# RF_in_v2.net
KiCad netlist of a schematic drawn in Altium Designer
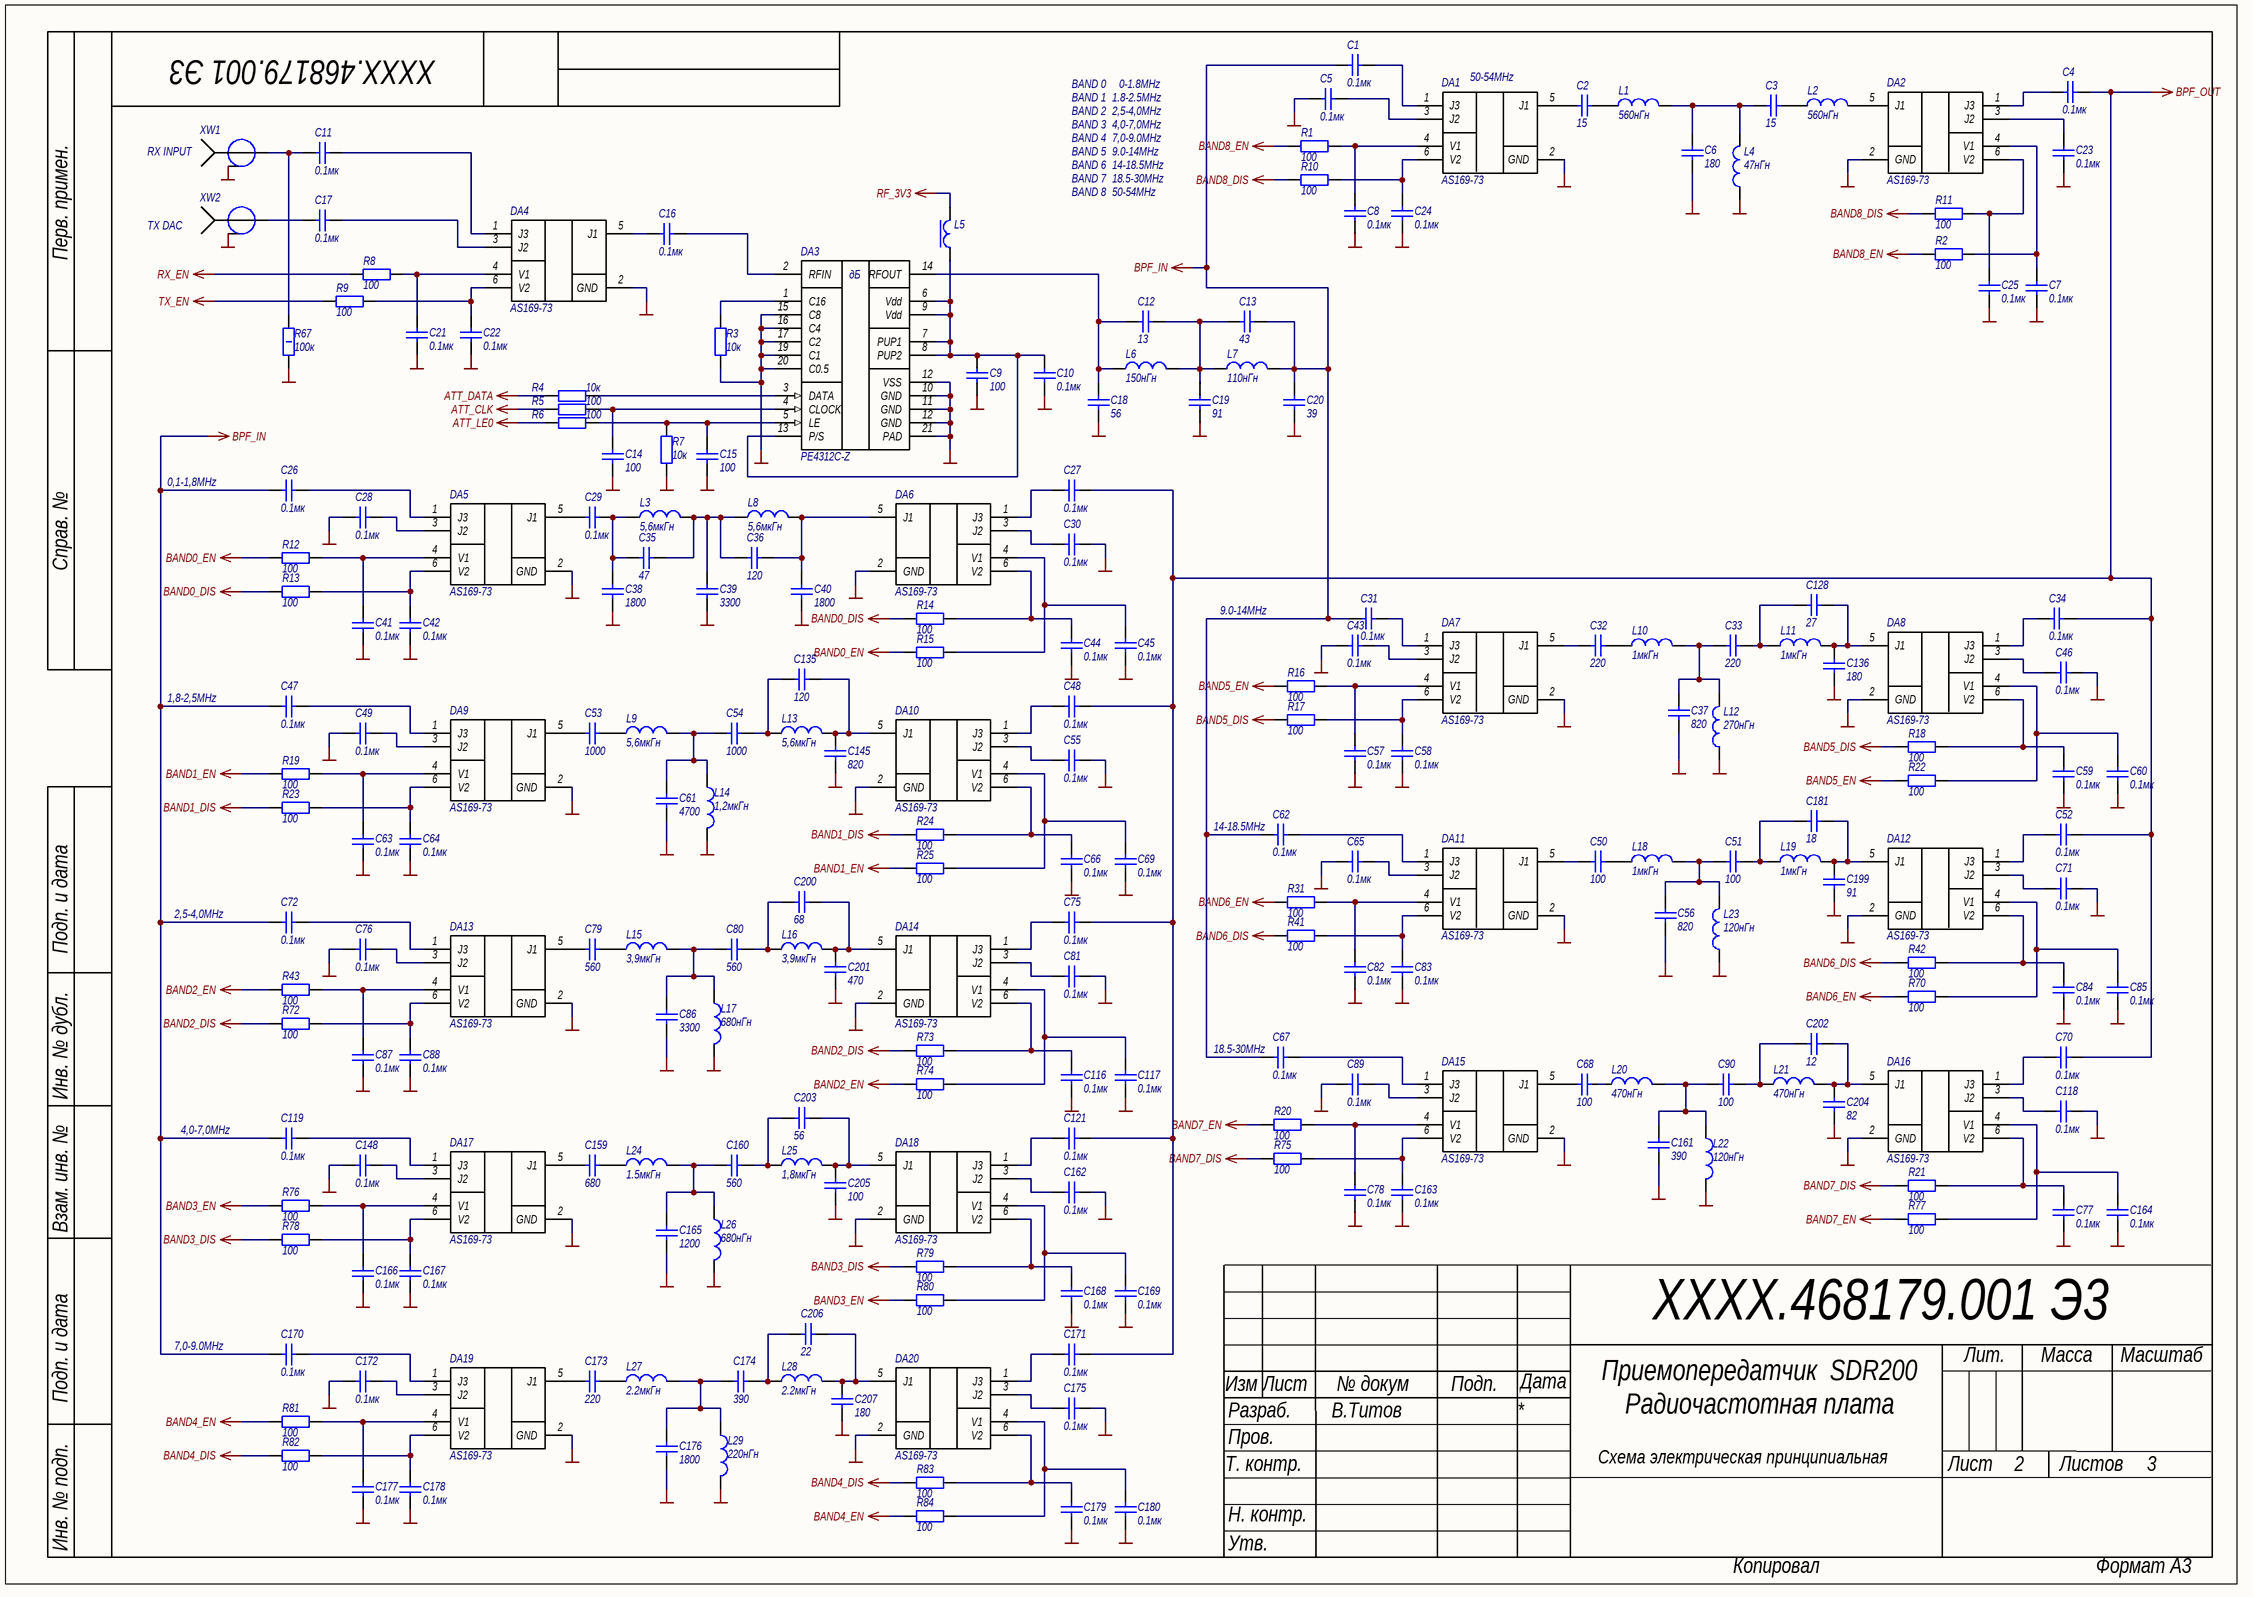
[diagram p0: RF_in_v2.SchDoc]

(export (version "E")
  (design (tool "Eeschema 10.0.6"))
  (components
    (comp (ref "C1")
      (value "0.1мк")
      (footprint "CAPC1005X06N")
      (description "Кер. ЧИП-конденсатор")
      (fields (field (name "TOLERANCE") "±10%"))
      (libsource (lib "nels") (part "Кер.ЧИП конд. 0402 0.1мкФ X7R 10%, 16В"))
    )
    (comp (ref "C2")
      (value "15")
      (footprint "CAPC1005X06N")
      (description "Кер. ЧИП-конденсатор")
      (fields (field (name "TOLERANCE") "±5%"))
      (libsource (lib "nels_caps") (part "Кер.ЧИП конд. 0402 15пФ NPO 5%, 50В"))
    )
    (comp (ref "C3")
      (value "15")
      (footprint "CAPC1005X06N")
      (description "Кер. ЧИП-конденсатор")
      (fields (field (name "TOLERANCE") "±5%"))
      (libsource (lib "nels_caps") (part "Кер.ЧИП конд. 0402 15пФ NPO 5%, 50В"))
    )
    (comp (ref "C4")
      (value "0.1мк")
      (footprint "CAPC1005X06N")
      (description "Кер. ЧИП-конденсатор")
      (fields (field (name "TOLERANCE") "±10%"))
      (libsource (lib "nels") (part "Кер.ЧИП конд. 0402 0.1мкФ X7R 10%, 16В"))
    )
    (comp (ref "C5")
      (value "0.1мк")
      (footprint "CAPC1005X06N")
      (description "Кер. ЧИП-конденсатор")
      (fields (field (name "TOLERANCE") "±10%"))
      (libsource (lib "nels") (part "Кер.ЧИП конд. 0402 0.1мкФ X7R 10%, 16В"))
    )
    (comp (ref "C6")
      (value "180")
      (footprint "CAPC1005X06N")
      (description "Кер. ЧИП-конденсатор")
      (fields (field (name "TOLERANCE") "±5%"))
      (libsource (lib "nels_caps") (part "Кер.ЧИП конд. 0402 180пФ NPO 5%, 50В"))
    )
    (comp (ref "C7")
      (value "0.1мк")
      (footprint "CAPC1005X06N")
      (description "Кер. ЧИП-конденсатор")
      (fields (field (name "TOLERANCE") "±10%"))
      (libsource (lib "nels") (part "Кер.ЧИП конд. 0402 0.1мкФ X7R 10%, 16В"))
    )
    (comp (ref "C8")
      (value "0.1мк")
      (footprint "CAPC1005X06N")
      (description "Кер. ЧИП-конденсатор")
      (fields (field (name "TOLERANCE") "±10%"))
      (libsource (lib "nels") (part "Кер.ЧИП конд. 0402 0.1мкФ X7R 10%, 16В"))
    )
    (comp (ref "C9")
      (value "100")
      (footprint "CAPC1005X06N")
      (description "Кер. ЧИП-конденсатор")
      (fields (field (name "TOLERANCE") "±5%"))
      (libsource (lib "nels_caps") (part "Кер.ЧИП конд. 0402 100пФ NPO 5%, 50В"))
    )
    (comp (ref "C10")
      (value "0.1мк")
      (footprint "CAPC1005X06N")
      (description "Кер. ЧИП-конденсатор")
      (fields (field (name "TOLERANCE") "±10%"))
      (libsource (lib "nels") (part "Кер.ЧИП конд. 0402 0.1мкФ X7R 10%, 16В"))
    )
    (comp (ref "C11")
      (value "0.1мк")
      (footprint "CAPC1005X06N")
      (description "Кер. ЧИП-конденсатор")
      (fields (field (name "TOLERANCE") "±10%"))
      (libsource (lib "nels") (part "Кер.ЧИП конд. 0402 0.1мкФ X7R 10%, 16В"))
    )
    (comp (ref "C12")
      (value "13")
      (footprint "CAPC1005X06N")
      (description "Кер. ЧИП-конденсатор")
      (fields (field (name "TOLERANCE") "±5%"))
      (libsource (lib "nels_caps") (part "Кер.ЧИП конд. 0402 13пФ NPO 5%, 50В"))
    )
    (comp (ref "C13")
      (value "43")
      (footprint "CAPC1005X06N")
      (description "Кер. ЧИП-конденсатор")
      (fields (field (name "TOLERANCE") "±5%"))
      (libsource (lib "nels_caps") (part "Кер.ЧИП конд. 0402 43пФ NPO 5%, 50В"))
    )
    (comp (ref "C14")
      (value "100")
      (footprint "CAPC1005X06N")
      (description "Кер. ЧИП-конденсатор")
      (fields (field (name "TOLERANCE") "±5%"))
      (libsource (lib "nels_caps") (part "Кер.ЧИП конд. 0402 100пФ NPO 5%, 50В"))
    )
    (comp (ref "C15")
      (value "100")
      (footprint "CAPC1005X06N")
      (description "Кер. ЧИП-конденсатор")
      (fields (field (name "TOLERANCE") "±5%"))
      (libsource (lib "nels_caps") (part "Кер.ЧИП конд. 0402 100пФ NPO 5%, 50В"))
    )
    (comp (ref "C16")
      (value "0.1мк")
      (footprint "CAPC1005X06N")
      (description "Кер. ЧИП-конденсатор")
      (fields (field (name "TOLERANCE") "±10%"))
      (libsource (lib "nels") (part "Кер.ЧИП конд. 0402 0.1мкФ X7R 10%, 16В"))
    )
    (comp (ref "C17")
      (value "0.1мк")
      (footprint "CAPC1005X06N")
      (description "Кер. ЧИП-конденсатор")
      (fields (field (name "TOLERANCE") "±10%"))
      (libsource (lib "nels") (part "Кер.ЧИП конд. 0402 0.1мкФ X7R 10%, 16В"))
    )
    (comp (ref "C18")
      (value "56")
      (footprint "CAPC1005X06N")
      (description "Кер. ЧИП-конденсатор")
      (fields (field (name "TOLERANCE") "±5%"))
      (libsource (lib "nels_caps") (part "Кер.ЧИП конд. 0402 56пФ NPO 5%, 50В"))
    )
    (comp (ref "C19")
      (value "91")
      (footprint "CAPC1005X06N")
      (description "Кер. ЧИП-конденсатор")
      (fields (field (name "TOLERANCE") "±5%"))
      (libsource (lib "nels_caps") (part "Кер.ЧИП конд. 0402 91пФ NPO 5%, 50В"))
    )
    (comp (ref "C20")
      (value "39")
      (footprint "CAPC1005X06N")
      (description "Кер. ЧИП-конденсатор")
      (fields (field (name "TOLERANCE") "±5%"))
      (libsource (lib "nels_caps") (part "Кер.ЧИП конд. 0402 39пФ NPO 5%, 50В"))
    )
    (comp (ref "C21")
      (value "0.1мк")
      (footprint "CAPC1005X06N")
      (description "Кер. ЧИП-конденсатор")
      (fields (field (name "TOLERANCE") "±10%"))
      (libsource (lib "nels") (part "Кер.ЧИП конд. 0402 0.1мкФ X7R 10%, 16В"))
    )
    (comp (ref "C22")
      (value "0.1мк")
      (footprint "CAPC1005X06N")
      (description "Кер. ЧИП-конденсатор")
      (fields (field (name "TOLERANCE") "±10%"))
      (libsource (lib "nels") (part "Кер.ЧИП конд. 0402 0.1мкФ X7R 10%, 16В"))
    )
    (comp (ref "C23")
      (value "0.1мк")
      (footprint "CAPC1005X06N")
      (description "Кер. ЧИП-конденсатор")
      (fields (field (name "TOLERANCE") "±10%"))
      (libsource (lib "nels") (part "Кер.ЧИП конд. 0402 0.1мкФ X7R 10%, 16В"))
    )
    (comp (ref "C24")
      (value "0.1мк")
      (footprint "CAPC1005X06N")
      (description "Кер. ЧИП-конденсатор")
      (fields (field (name "TOLERANCE") "±10%"))
      (libsource (lib "nels") (part "Кер.ЧИП конд. 0402 0.1мкФ X7R 10%, 16В"))
    )
    (comp (ref "C25")
      (value "0.1мк")
      (footprint "CAPC1005X06N")
      (description "Кер. ЧИП-конденсатор")
      (fields (field (name "TOLERANCE") "±10%"))
      (libsource (lib "nels") (part "Кер.ЧИП конд. 0402 0.1мкФ X7R 10%, 16В"))
    )
    (comp (ref "C26")
      (value "0.1мк")
      (footprint "CAPC1005X06N")
      (description "Кер. ЧИП-конденсатор")
      (fields (field (name "TOLERANCE") "±10%"))
      (libsource (lib "nels") (part "Кер.ЧИП конд. 0402 0.1мкФ X7R 10%, 16В"))
    )
    (comp (ref "C27")
      (value "0.1мк")
      (footprint "CAPC1005X06N")
      (description "Кер. ЧИП-конденсатор")
      (fields (field (name "TOLERANCE") "±10%"))
      (libsource (lib "nels") (part "Кер.ЧИП конд. 0402 0.1мкФ X7R 10%, 16В"))
    )
    (comp (ref "C28")
      (value "0.1мк")
      (footprint "CAPC1005X06N")
      (description "Кер. ЧИП-конденсатор")
      (fields (field (name "TOLERANCE") "±10%"))
      (libsource (lib "nels") (part "Кер.ЧИП конд. 0402 0.1мкФ X7R 10%, 16В"))
    )
    (comp (ref "C29")
      (value "0.1мк")
      (footprint "CAPC1005X06N")
      (description "Кер. ЧИП-конденсатор")
      (fields (field (name "TOLERANCE") "±10%"))
      (libsource (lib "nels") (part "Кер.ЧИП конд. 0402 0.1мкФ X7R 10%, 16В"))
    )
    (comp (ref "C30")
      (value "0.1мк")
      (footprint "CAPC1005X06N")
      (description "Кер. ЧИП-конденсатор")
      (fields (field (name "TOLERANCE") "±10%"))
      (libsource (lib "nels") (part "Кер.ЧИП конд. 0402 0.1мкФ X7R 10%, 16В"))
    )
    (comp (ref "C31")
      (value "0.1мк")
      (footprint "CAPC1005X06N")
      (description "Кер. ЧИП-конденсатор")
      (fields (field (name "TOLERANCE") "±10%"))
      (libsource (lib "nels") (part "Кер.ЧИП конд. 0402 0.1мкФ X7R 10%, 16В"))
    )
    (comp (ref "C32")
      (value "220")
      (footprint "CAPC1005X06N")
      (description "Кер. ЧИП-конденсатор")
      (fields (field (name "TOLERANCE") "±5%"))
      (libsource (lib "nels_caps") (part "Кер.ЧИП конд. 0402 220пФ NPO 5%, 50В"))
    )
    (comp (ref "C33")
      (value "220")
      (footprint "CAPC1005X06N")
      (description "Кер. ЧИП-конденсатор")
      (fields (field (name "TOLERANCE") "±5%"))
      (libsource (lib "nels_caps") (part "Кер.ЧИП конд. 0402 220пФ NPO 5%, 50В"))
    )
    (comp (ref "C34")
      (value "0.1мк")
      (footprint "CAPC1005X06N")
      (description "Кер. ЧИП-конденсатор")
      (fields (field (name "TOLERANCE") "±10%"))
      (libsource (lib "nels") (part "Кер.ЧИП конд. 0402 0.1мкФ X7R 10%, 16В"))
    )
    (comp (ref "C35")
      (value "47")
      (footprint "CAPC1005X06N")
      (description "Кер. ЧИП-конденсатор")
      (fields (field (name "TOLERANCE") "±5%"))
      (libsource (lib "nels_caps") (part "Кер.ЧИП конд. 0402 47пФ NPO 5%, 50В"))
    )
    (comp (ref "C36")
      (value "120")
      (footprint "CAPC1005X06N")
      (description "Кер. ЧИП-конденсатор")
      (fields (field (name "TOLERANCE") "±5%"))
      (libsource (lib "nels_caps") (part "Кер.ЧИП конд. 0402 120пФ NPO 5%, 50В"))
    )
    (comp (ref "C37")
      (value "820")
      (footprint "CAPC1005X06N")
      (description "Кер. ЧИП-конденсатор")
      (fields (field (name "TOLERANCE") "±5%"))
      (libsource (lib "nels_caps") (part "Кер.ЧИП конд. 0402 820пФ NP0 5%, 50В"))
    )
    (comp (ref "C38")
      (value "1800")
      (footprint "CAPC1005X06N")
      (description "Кер. ЧИП-конденсатор")
      (fields (field (name "TOLERANCE") "±20%"))
      (libsource (lib "nels_caps") (part "Кер.ЧИП конд. 0402 1800пФ X7R 10%, 50В"))
    )
    (comp (ref "C39")
      (value "3300")
      (footprint "CAPC1005X06N")
      (description "Кер. ЧИП-конденсатор")
      (fields (field (name "TOLERANCE") "±20%"))
      (libsource (lib "nels_caps") (part "Кер.ЧИП конд. 0402 3300пФ X7R 10%, 50В"))
    )
    (comp (ref "C40")
      (value "1800")
      (footprint "CAPC1005X06N")
      (description "Кер. ЧИП-конденсатор")
      (fields (field (name "TOLERANCE") "±20%"))
      (libsource (lib "nels_caps") (part "Кер.ЧИП конд. 0402 1800пФ X7R 10%, 50В"))
    )
    (comp (ref "C41")
      (value "0.1мк")
      (footprint "CAPC1005X06N")
      (description "Кер. ЧИП-конденсатор")
      (fields (field (name "TOLERANCE") "±10%"))
      (libsource (lib "nels") (part "Кер.ЧИП конд. 0402 0.1мкФ X7R 10%, 16В"))
    )
    (comp (ref "C42")
      (value "0.1мк")
      (footprint "CAPC1005X06N")
      (description "Кер. ЧИП-конденсатор")
      (fields (field (name "TOLERANCE") "±10%"))
      (libsource (lib "nels") (part "Кер.ЧИП конд. 0402 0.1мкФ X7R 10%, 16В"))
    )
    (comp (ref "C43")
      (value "0.1мк")
      (footprint "CAPC1005X06N")
      (description "Кер. ЧИП-конденсатор")
      (fields (field (name "TOLERANCE") "±10%"))
      (libsource (lib "nels") (part "Кер.ЧИП конд. 0402 0.1мкФ X7R 10%, 16В"))
    )
    (comp (ref "C44")
      (value "0.1мк")
      (footprint "CAPC1005X06N")
      (description "Кер. ЧИП-конденсатор")
      (fields (field (name "TOLERANCE") "±10%"))
      (libsource (lib "nels") (part "Кер.ЧИП конд. 0402 0.1мкФ X7R 10%, 16В"))
    )
    (comp (ref "C45")
      (value "0.1мк")
      (footprint "CAPC1005X06N")
      (description "Кер. ЧИП-конденсатор")
      (fields (field (name "TOLERANCE") "±10%"))
      (libsource (lib "nels") (part "Кер.ЧИП конд. 0402 0.1мкФ X7R 10%, 16В"))
    )
    (comp (ref "C46")
      (value "0.1мк")
      (footprint "CAPC1005X06N")
      (description "Кер. ЧИП-конденсатор")
      (fields (field (name "TOLERANCE") "±10%"))
      (libsource (lib "nels") (part "Кер.ЧИП конд. 0402 0.1мкФ X7R 10%, 16В"))
    )
    (comp (ref "C47")
      (value "0.1мк")
      (footprint "CAPC1005X06N")
      (description "Кер. ЧИП-конденсатор")
      (fields (field (name "TOLERANCE") "±10%"))
      (libsource (lib "nels") (part "Кер.ЧИП конд. 0402 0.1мкФ X7R 10%, 16В"))
    )
    (comp (ref "C48")
      (value "0.1мк")
      (footprint "CAPC1005X06N")
      (description "Кер. ЧИП-конденсатор")
      (fields (field (name "TOLERANCE") "±10%"))
      (libsource (lib "nels") (part "Кер.ЧИП конд. 0402 0.1мкФ X7R 10%, 16В"))
    )
    (comp (ref "C49")
      (value "0.1мк")
      (footprint "CAPC1005X06N")
      (description "Кер. ЧИП-конденсатор")
      (fields (field (name "TOLERANCE") "±10%"))
      (libsource (lib "nels") (part "Кер.ЧИП конд. 0402 0.1мкФ X7R 10%, 16В"))
    )
    (comp (ref "C50")
      (value "100")
      (footprint "CAPC1005X06N")
      (description "Кер. ЧИП-конденсатор")
      (fields (field (name "TOLERANCE") "±5%"))
      (libsource (lib "nels_caps") (part "Кер.ЧИП конд. 0402 100пФ NPO 5%, 50В"))
    )
    (comp (ref "C51")
      (value "100")
      (footprint "CAPC1005X06N")
      (description "Кер. ЧИП-конденсатор")
      (fields (field (name "TOLERANCE") "±5%"))
      (libsource (lib "nels_caps") (part "Кер.ЧИП конд. 0402 100пФ NPO 5%, 50В"))
    )
    (comp (ref "C52")
      (value "0.1мк")
      (footprint "CAPC1005X06N")
      (description "Кер. ЧИП-конденсатор")
      (fields (field (name "TOLERANCE") "±10%"))
      (libsource (lib "nels") (part "Кер.ЧИП конд. 0402 0.1мкФ X7R 10%, 16В"))
    )
    (comp (ref "C53")
      (value "1000")
      (footprint "CAPC1005X06N")
      (description "Кер. ЧИП-конденсатор")
      (fields (field (name "TOLERANCE") "±5%"))
      (libsource (lib "nels_caps") (part "Кер.ЧИП конд. 0402 1000пФ NP0 5%, 50В"))
    )
    (comp (ref "C54")
      (value "1000")
      (footprint "CAPC1005X06N")
      (description "Кер. ЧИП-конденсатор")
      (fields (field (name "TOLERANCE") "±5%"))
      (libsource (lib "nels_caps") (part "Кер.ЧИП конд. 0402 1000пФ NP0 5%, 50В"))
    )
    (comp (ref "C55")
      (value "0.1мк")
      (footprint "CAPC1005X06N")
      (description "Кер. ЧИП-конденсатор")
      (fields (field (name "TOLERANCE") "±10%"))
      (libsource (lib "nels") (part "Кер.ЧИП конд. 0402 0.1мкФ X7R 10%, 16В"))
    )
    (comp (ref "C56")
      (value "820")
      (footprint "CAPC1005X06N")
      (description "Кер. ЧИП-конденсатор")
      (fields (field (name "TOLERANCE") "±5%"))
      (libsource (lib "nels_caps") (part "Кер.ЧИП конд. 0402 820пФ NP0 5%, 50В"))
    )
    (comp (ref "C57")
      (value "0.1мк")
      (footprint "CAPC1005X06N")
      (description "Кер. ЧИП-конденсатор")
      (fields (field (name "TOLERANCE") "±10%"))
      (libsource (lib "nels") (part "Кер.ЧИП конд. 0402 0.1мкФ X7R 10%, 16В"))
    )
    (comp (ref "C58")
      (value "0.1мк")
      (footprint "CAPC1005X06N")
      (description "Кер. ЧИП-конденсатор")
      (fields (field (name "TOLERANCE") "±10%"))
      (libsource (lib "nels") (part "Кер.ЧИП конд. 0402 0.1мкФ X7R 10%, 16В"))
    )
    (comp (ref "C59")
      (value "0.1мк")
      (footprint "CAPC1005X06N")
      (description "Кер. ЧИП-конденсатор")
      (fields (field (name "TOLERANCE") "±10%"))
      (libsource (lib "nels") (part "Кер.ЧИП конд. 0402 0.1мкФ X7R 10%, 16В"))
    )
    (comp (ref "C60")
      (value "0.1мк")
      (footprint "CAPC1005X06N")
      (description "Кер. ЧИП-конденсатор")
      (fields (field (name "TOLERANCE") "±10%"))
      (libsource (lib "nels") (part "Кер.ЧИП конд. 0402 0.1мкФ X7R 10%, 16В"))
    )
    (comp (ref "C61")
      (value "4700")
      (footprint "CAPC1005X06N")
      (description "Кер. ЧИП-конденсатор")
      (fields (field (name "TOLERANCE") "±20%"))
      (libsource (lib "nels_caps") (part "Кер.ЧИП конд. 0402 4700пФ X7R 10%, 50В"))
    )
    (comp (ref "C62")
      (value "0.1мк")
      (footprint "CAPC1005X06N")
      (description "Кер. ЧИП-конденсатор")
      (fields (field (name "TOLERANCE") "±10%"))
      (libsource (lib "nels") (part "Кер.ЧИП конд. 0402 0.1мкФ X7R 10%, 16В"))
    )
    (comp (ref "C63")
      (value "0.1мк")
      (footprint "CAPC1005X06N")
      (description "Кер. ЧИП-конденсатор")
      (fields (field (name "TOLERANCE") "±10%"))
      (libsource (lib "nels") (part "Кер.ЧИП конд. 0402 0.1мкФ X7R 10%, 16В"))
    )
    (comp (ref "C64")
      (value "0.1мк")
      (footprint "CAPC1005X06N")
      (description "Кер. ЧИП-конденсатор")
      (fields (field (name "TOLERANCE") "±10%"))
      (libsource (lib "nels") (part "Кер.ЧИП конд. 0402 0.1мкФ X7R 10%, 16В"))
    )
    (comp (ref "C65")
      (value "0.1мк")
      (footprint "CAPC1005X06N")
      (description "Кер. ЧИП-конденсатор")
      (fields (field (name "TOLERANCE") "±10%"))
      (libsource (lib "nels") (part "Кер.ЧИП конд. 0402 0.1мкФ X7R 10%, 16В"))
    )
    (comp (ref "C66")
      (value "0.1мк")
      (footprint "CAPC1005X06N")
      (description "Кер. ЧИП-конденсатор")
      (fields (field (name "TOLERANCE") "±10%"))
      (libsource (lib "nels") (part "Кер.ЧИП конд. 0402 0.1мкФ X7R 10%, 16В"))
    )
    (comp (ref "C67")
      (value "0.1мк")
      (footprint "CAPC1005X06N")
      (description "Кер. ЧИП-конденсатор")
      (fields (field (name "TOLERANCE") "±10%"))
      (libsource (lib "nels") (part "Кер.ЧИП конд. 0402 0.1мкФ X7R 10%, 16В"))
    )
    (comp (ref "C68")
      (value "100")
      (footprint "CAPC1005X06N")
      (description "Кер. ЧИП-конденсатор")
      (fields (field (name "TOLERANCE") "±5%"))
      (libsource (lib "nels_caps") (part "Кер.ЧИП конд. 0402 100пФ NPO 5%, 50В"))
    )
    (comp (ref "C69")
      (value "0.1мк")
      (footprint "CAPC1005X06N")
      (description "Кер. ЧИП-конденсатор")
      (fields (field (name "TOLERANCE") "±10%"))
      (libsource (lib "nels") (part "Кер.ЧИП конд. 0402 0.1мкФ X7R 10%, 16В"))
    )
    (comp (ref "C70")
      (value "0.1мк")
      (footprint "CAPC1005X06N")
      (description "Кер. ЧИП-конденсатор")
      (fields (field (name "TOLERANCE") "±10%"))
      (libsource (lib "nels") (part "Кер.ЧИП конд. 0402 0.1мкФ X7R 10%, 16В"))
    )
    (comp (ref "C71")
      (value "0.1мк")
      (footprint "CAPC1005X06N")
      (description "Кер. ЧИП-конденсатор")
      (fields (field (name "TOLERANCE") "±10%"))
      (libsource (lib "nels") (part "Кер.ЧИП конд. 0402 0.1мкФ X7R 10%, 16В"))
    )
    (comp (ref "C72")
      (value "0.1мк")
      (footprint "CAPC1005X06N")
      (description "Кер. ЧИП-конденсатор")
      (fields (field (name "TOLERANCE") "±10%"))
      (libsource (lib "nels") (part "Кер.ЧИП конд. 0402 0.1мкФ X7R 10%, 16В"))
    )
    (comp (ref "C75")
      (value "0.1мк")
      (footprint "CAPC1005X06N")
      (description "Кер. ЧИП-конденсатор")
      (fields (field (name "TOLERANCE") "±10%"))
      (libsource (lib "nels") (part "Кер.ЧИП конд. 0402 0.1мкФ X7R 10%, 16В"))
    )
    (comp (ref "C76")
      (value "0.1мк")
      (footprint "CAPC1005X06N")
      (description "Кер. ЧИП-конденсатор")
      (fields (field (name "TOLERANCE") "±10%"))
      (libsource (lib "nels") (part "Кер.ЧИП конд. 0402 0.1мкФ X7R 10%, 16В"))
    )
    (comp (ref "C77")
      (value "0.1мк")
      (footprint "CAPC1005X06N")
      (description "Кер. ЧИП-конденсатор")
      (fields (field (name "TOLERANCE") "±10%"))
      (libsource (lib "nels") (part "Кер.ЧИП конд. 0402 0.1мкФ X7R 10%, 16В"))
    )
    (comp (ref "C78")
      (value "0.1мк")
      (footprint "CAPC1005X06N")
      (description "Кер. ЧИП-конденсатор")
      (fields (field (name "TOLERANCE") "±10%"))
      (libsource (lib "nels") (part "Кер.ЧИП конд. 0402 0.1мкФ X7R 10%, 16В"))
    )
    (comp (ref "C79")
      (value "560")
      (footprint "CAPC1005X06N")
      (description "Кер. ЧИП-конденсатор")
      (fields (field (name "TOLERANCE") "±5%"))
      (libsource (lib "nels_caps") (part "Кер.ЧИП конд. 0402 560пФ NP0 5%, 50В"))
    )
    (comp (ref "C80")
      (value "560")
      (footprint "CAPC1005X06N")
      (description "Кер. ЧИП-конденсатор")
      (fields (field (name "TOLERANCE") "±5%"))
      (libsource (lib "nels_caps") (part "Кер.ЧИП конд. 0402 560пФ NP0 5%, 50В"))
    )
    (comp (ref "C81")
      (value "0.1мк")
      (footprint "CAPC1005X06N")
      (description "Кер. ЧИП-конденсатор")
      (fields (field (name "TOLERANCE") "±10%"))
      (libsource (lib "nels") (part "Кер.ЧИП конд. 0402 0.1мкФ X7R 10%, 16В"))
    )
    (comp (ref "C82")
      (value "0.1мк")
      (footprint "CAPC1005X06N")
      (description "Кер. ЧИП-конденсатор")
      (fields (field (name "TOLERANCE") "±10%"))
      (libsource (lib "nels") (part "Кер.ЧИП конд. 0402 0.1мкФ X7R 10%, 16В"))
    )
    (comp (ref "C83")
      (value "0.1мк")
      (footprint "CAPC1005X06N")
      (description "Кер. ЧИП-конденсатор")
      (fields (field (name "TOLERANCE") "±10%"))
      (libsource (lib "nels") (part "Кер.ЧИП конд. 0402 0.1мкФ X7R 10%, 16В"))
    )
    (comp (ref "C84")
      (value "0.1мк")
      (footprint "CAPC1005X06N")
      (description "Кер. ЧИП-конденсатор")
      (fields (field (name "TOLERANCE") "±10%"))
      (libsource (lib "nels") (part "Кер.ЧИП конд. 0402 0.1мкФ X7R 10%, 16В"))
    )
    (comp (ref "C85")
      (value "0.1мк")
      (footprint "CAPC1005X06N")
      (description "Кер. ЧИП-конденсатор")
      (fields (field (name "TOLERANCE") "±10%"))
      (libsource (lib "nels") (part "Кер.ЧИП конд. 0402 0.1мкФ X7R 10%, 16В"))
    )
    (comp (ref "C86")
      (value "3300")
      (footprint "CAPC1005X06N")
      (description "Кер. ЧИП-конденсатор")
      (fields (field (name "TOLERANCE") "±20%"))
      (libsource (lib "nels_caps") (part "Кер.ЧИП конд. 0402 3300пФ X7R 10%, 50В"))
    )
    (comp (ref "C87")
      (value "0.1мк")
      (footprint "CAPC1005X06N")
      (description "Кер. ЧИП-конденсатор")
      (fields (field (name "TOLERANCE") "±10%"))
      (libsource (lib "nels") (part "Кер.ЧИП конд. 0402 0.1мкФ X7R 10%, 16В"))
    )
    (comp (ref "C88")
      (value "0.1мк")
      (footprint "CAPC1005X06N")
      (description "Кер. ЧИП-конденсатор")
      (fields (field (name "TOLERANCE") "±10%"))
      (libsource (lib "nels") (part "Кер.ЧИП конд. 0402 0.1мкФ X7R 10%, 16В"))
    )
    (comp (ref "C89")
      (value "0.1мк")
      (footprint "CAPC1005X06N")
      (description "Кер. ЧИП-конденсатор")
      (fields (field (name "TOLERANCE") "±10%"))
      (libsource (lib "nels") (part "Кер.ЧИП конд. 0402 0.1мкФ X7R 10%, 16В"))
    )
    (comp (ref "C90")
      (value "100")
      (footprint "CAPC1005X06N")
      (description "Кер. ЧИП-конденсатор")
      (fields (field (name "TOLERANCE") "±5%"))
      (libsource (lib "nels_caps") (part "Кер.ЧИП конд. 0402 100пФ NPO 5%, 50В"))
    )
    (comp (ref "C116")
      (value "0.1мк")
      (footprint "CAPC1005X06N")
      (description "Кер. ЧИП-конденсатор")
      (fields (field (name "TOLERANCE") "±10%"))
      (libsource (lib "nels") (part "Кер.ЧИП конд. 0402 0.1мкФ X7R 10%, 16В"))
    )
    (comp (ref "C117")
      (value "0.1мк")
      (footprint "CAPC1005X06N")
      (description "Кер. ЧИП-конденсатор")
      (fields (field (name "TOLERANCE") "±10%"))
      (libsource (lib "nels") (part "Кер.ЧИП конд. 0402 0.1мкФ X7R 10%, 16В"))
    )
    (comp (ref "C118")
      (value "0.1мк")
      (footprint "CAPC1005X06N")
      (description "Кер. ЧИП-конденсатор")
      (fields (field (name "TOLERANCE") "±10%"))
      (libsource (lib "nels") (part "Кер.ЧИП конд. 0402 0.1мкФ X7R 10%, 16В"))
    )
    (comp (ref "C119")
      (value "0.1мк")
      (footprint "CAPC1005X06N")
      (description "Кер. ЧИП-конденсатор")
      (fields (field (name "TOLERANCE") "±10%"))
      (libsource (lib "nels") (part "Кер.ЧИП конд. 0402 0.1мкФ X7R 10%, 16В"))
    )
    (comp (ref "C121")
      (value "0.1мк")
      (footprint "CAPC1005X06N")
      (description "Кер. ЧИП-конденсатор")
      (fields (field (name "TOLERANCE") "±10%"))
      (libsource (lib "nels") (part "Кер.ЧИП конд. 0402 0.1мкФ X7R 10%, 16В"))
    )
    (comp (ref "C128")
      (value "27")
      (footprint "CAPC1005X06N")
      (description "Кер. ЧИП-конденсатор")
      (fields (field (name "TOLERANCE") "±5%"))
      (libsource (lib "nels_caps") (part "Кер.ЧИП конд. 0402 27пФ NPO 5%, 50В"))
    )
    (comp (ref "C135")
      (value "120")
      (footprint "CAPC1005X06N")
      (description "Кер. ЧИП-конденсатор")
      (fields (field (name "TOLERANCE") "±5%"))
      (libsource (lib "nels_caps") (part "Кер.ЧИП конд. 0402 120пФ NPO 5%, 50В"))
    )
    (comp (ref "C136")
      (value "180")
      (footprint "CAPC1005X06N")
      (description "Кер. ЧИП-конденсатор")
      (fields (field (name "TOLERANCE") "±5%"))
      (libsource (lib "nels_caps") (part "Кер.ЧИП конд. 0402 180пФ NPO 5%, 50В"))
    )
    (comp (ref "C145")
      (value "820")
      (footprint "CAPC1005X06N")
      (description "Кер. ЧИП-конденсатор")
      (fields (field (name "TOLERANCE") "±5%"))
      (libsource (lib "nels_caps") (part "Кер.ЧИП конд. 0402 820пФ NP0 5%, 50В"))
    )
    (comp (ref "C148")
      (value "0.1мк")
      (footprint "CAPC1005X06N")
      (description "Кер. ЧИП-конденсатор")
      (fields (field (name "TOLERANCE") "±10%"))
      (libsource (lib "nels") (part "Кер.ЧИП конд. 0402 0.1мкФ X7R 10%, 16В"))
    )
    (comp (ref "C159")
      (value "680")
      (footprint "CAPC1005X06N")
      (description "Кер. ЧИП-конденсатор")
      (fields (field (name "TOLERANCE") "±5%"))
      (libsource (lib "nels_caps") (part "Кер.ЧИП конд. 0402 680пФ NP0 5%, 50В"))
    )
    (comp (ref "C160")
      (value "560")
      (footprint "CAPC1005X06N")
      (description "Кер. ЧИП-конденсатор")
      (fields (field (name "TOLERANCE") "±5%"))
      (libsource (lib "nels_caps") (part "Кер.ЧИП конд. 0402 560пФ NP0 5%, 50В"))
    )
    (comp (ref "C161")
      (value "390")
      (footprint "CAPC1005X06N")
      (description "Кер. ЧИП-конденсатор")
      (fields (field (name "TOLERANCE") "±5%"))
      (libsource (lib "nels_caps") (part "Кер.ЧИП конд. 0402 390пФ NP0 5%, 50В"))
    )
    (comp (ref "C162")
      (value "0.1мк")
      (footprint "CAPC1005X06N")
      (description "Кер. ЧИП-конденсатор")
      (fields (field (name "TOLERANCE") "±10%"))
      (libsource (lib "nels") (part "Кер.ЧИП конд. 0402 0.1мкФ X7R 10%, 16В"))
    )
    (comp (ref "C163")
      (value "0.1мк")
      (footprint "CAPC1005X06N")
      (description "Кер. ЧИП-конденсатор")
      (fields (field (name "TOLERANCE") "±10%"))
      (libsource (lib "nels") (part "Кер.ЧИП конд. 0402 0.1мкФ X7R 10%, 16В"))
    )
    (comp (ref "C164")
      (value "0.1мк")
      (footprint "CAPC1005X06N")
      (description "Кер. ЧИП-конденсатор")
      (fields (field (name "TOLERANCE") "±10%"))
      (libsource (lib "nels") (part "Кер.ЧИП конд. 0402 0.1мкФ X7R 10%, 16В"))
    )
    (comp (ref "C165")
      (value "1200")
      (footprint "CAPC1005X06N")
      (description "Кер. ЧИП-конденсатор")
      (fields (field (name "TOLERANCE") "±20%"))
      (libsource (lib "nels_caps") (part "Кер.ЧИП конд. 0402 1200пФ X7R 10%, 50В"))
    )
    (comp (ref "C166")
      (value "0.1мк")
      (footprint "CAPC1005X06N")
      (description "Кер. ЧИП-конденсатор")
      (fields (field (name "TOLERANCE") "±10%"))
      (libsource (lib "nels") (part "Кер.ЧИП конд. 0402 0.1мкФ X7R 10%, 16В"))
    )
    (comp (ref "C167")
      (value "0.1мк")
      (footprint "CAPC1005X06N")
      (description "Кер. ЧИП-конденсатор")
      (fields (field (name "TOLERANCE") "±10%"))
      (libsource (lib "nels") (part "Кер.ЧИП конд. 0402 0.1мкФ X7R 10%, 16В"))
    )
    (comp (ref "C168")
      (value "0.1мк")
      (footprint "CAPC1005X06N")
      (description "Кер. ЧИП-конденсатор")
      (fields (field (name "TOLERANCE") "±10%"))
      (libsource (lib "nels") (part "Кер.ЧИП конд. 0402 0.1мкФ X7R 10%, 16В"))
    )
    (comp (ref "C169")
      (value "0.1мк")
      (footprint "CAPC1005X06N")
      (description "Кер. ЧИП-конденсатор")
      (fields (field (name "TOLERANCE") "±10%"))
      (libsource (lib "nels") (part "Кер.ЧИП конд. 0402 0.1мкФ X7R 10%, 16В"))
    )
    (comp (ref "C170")
      (value "0.1мк")
      (footprint "CAPC1005X06N")
      (description "Кер. ЧИП-конденсатор")
      (fields (field (name "TOLERANCE") "±10%"))
      (libsource (lib "nels") (part "Кер.ЧИП конд. 0402 0.1мкФ X7R 10%, 16В"))
    )
    (comp (ref "C171")
      (value "0.1мк")
      (footprint "CAPC1005X06N")
      (description "Кер. ЧИП-конденсатор")
      (fields (field (name "TOLERANCE") "±10%"))
      (libsource (lib "nels") (part "Кер.ЧИП конд. 0402 0.1мкФ X7R 10%, 16В"))
    )
    (comp (ref "C172")
      (value "0.1мк")
      (footprint "CAPC1005X06N")
      (description "Кер. ЧИП-конденсатор")
      (fields (field (name "TOLERANCE") "±10%"))
      (libsource (lib "nels") (part "Кер.ЧИП конд. 0402 0.1мкФ X7R 10%, 16В"))
    )
    (comp (ref "C173")
      (value "220")
      (footprint "CAPC1005X06N")
      (description "Кер. ЧИП-конденсатор")
      (fields (field (name "TOLERANCE") "±5%"))
      (libsource (lib "nels_caps") (part "Кер.ЧИП конд. 0402 220пФ NPO 5%, 50В"))
    )
    (comp (ref "C174")
      (value "390")
      (footprint "CAPC1005X06N")
      (description "Кер. ЧИП-конденсатор")
      (fields (field (name "TOLERANCE") "±5%"))
      (libsource (lib "nels_caps") (part "Кер.ЧИП конд. 0402 390пФ NP0 5%, 50В"))
    )
    (comp (ref "C175")
      (value "0.1мк")
      (footprint "CAPC1005X06N")
      (description "Кер. ЧИП-конденсатор")
      (fields (field (name "TOLERANCE") "±10%"))
      (libsource (lib "nels") (part "Кер.ЧИП конд. 0402 0.1мкФ X7R 10%, 16В"))
    )
    (comp (ref "C176")
      (value "1800")
      (footprint "CAPC1005X06N")
      (description "Кер. ЧИП-конденсатор")
      (fields (field (name "TOLERANCE") "±20%"))
      (libsource (lib "nels_caps") (part "Кер.ЧИП конд. 0402 1800пФ X7R 10%, 50В"))
    )
    (comp (ref "C177")
      (value "0.1мк")
      (footprint "CAPC1005X06N")
      (description "Кер. ЧИП-конденсатор")
      (fields (field (name "TOLERANCE") "±10%"))
      (libsource (lib "nels") (part "Кер.ЧИП конд. 0402 0.1мкФ X7R 10%, 16В"))
    )
    (comp (ref "C178")
      (value "0.1мк")
      (footprint "CAPC1005X06N")
      (description "Кер. ЧИП-конденсатор")
      (fields (field (name "TOLERANCE") "±10%"))
      (libsource (lib "nels") (part "Кер.ЧИП конд. 0402 0.1мкФ X7R 10%, 16В"))
    )
    (comp (ref "C179")
      (value "0.1мк")
      (footprint "CAPC1005X06N")
      (description "Кер. ЧИП-конденсатор")
      (fields (field (name "TOLERANCE") "±10%"))
      (libsource (lib "nels") (part "Кер.ЧИП конд. 0402 0.1мкФ X7R 10%, 16В"))
    )
    (comp (ref "C180")
      (value "0.1мк")
      (footprint "CAPC1005X06N")
      (description "Кер. ЧИП-конденсатор")
      (fields (field (name "TOLERANCE") "±10%"))
      (libsource (lib "nels") (part "Кер.ЧИП конд. 0402 0.1мкФ X7R 10%, 16В"))
    )
    (comp (ref "C181")
      (value "18")
      (footprint "CAPC1005X06N")
      (description "Кер. ЧИП-конденсатор")
      (fields (field (name "TOLERANCE") "±5%"))
      (libsource (lib "nels_caps") (part "Кер.ЧИП конд. 0402 18пФ NPO 5%, 50В"))
    )
    (comp (ref "C199")
      (value "91")
      (footprint "CAPC1005X06N")
      (description "Кер. ЧИП-конденсатор")
      (fields (field (name "TOLERANCE") "±5%"))
      (libsource (lib "nels_caps") (part "Кер.ЧИП конд. 0402 91пФ NPO 5%, 50В"))
    )
    (comp (ref "C200")
      (value "68")
      (footprint "CAPC1005X06N")
      (description "Кер. ЧИП-конденсатор")
      (fields (field (name "TOLERANCE") "±5%"))
      (libsource (lib "nels_caps") (part "Кер.ЧИП конд. 0402 68пФ NPO 5%, 50В"))
    )
    (comp (ref "C201")
      (value "470")
      (footprint "CAPC1005X06N")
      (description "Кер. ЧИП-конденсатор")
      (fields (field (name "TOLERANCE") "±5%"))
      (libsource (lib "nels_caps") (part "Кер.ЧИП конд. 0402 470пФ NP0 5%, 50В"))
    )
    (comp (ref "C202")
      (value "12")
      (footprint "CAPC1005X06N")
      (description "Кер. ЧИП-конденсатор")
      (fields (field (name "TOLERANCE") "±5%"))
      (libsource (lib "nels_caps") (part "Кер.ЧИП конд. 0402 12пФ NPO 5%, 50В"))
    )
    (comp (ref "C203")
      (value "56")
      (footprint "CAPC1005X06N")
      (description "Кер. ЧИП-конденсатор")
      (fields (field (name "TOLERANCE") "±5%"))
      (libsource (lib "nels_caps") (part "Кер.ЧИП конд. 0402 56пФ NPO 5%, 50В"))
    )
    (comp (ref "C204")
      (value "82")
      (footprint "CAPC1005X06N")
      (description "Кер. ЧИП-конденсатор")
      (fields (field (name "TOLERANCE") "±5%"))
      (libsource (lib "nels_caps") (part "Кер.ЧИП конд. 0402 82пФ NPO 5%, 50В"))
    )
    (comp (ref "C205")
      (value "100")
      (footprint "CAPC1005X06N")
      (description "Кер. ЧИП-конденсатор")
      (fields (field (name "TOLERANCE") "±5%"))
      (libsource (lib "nels_caps") (part "Кер.ЧИП конд. 0402 100пФ NPO 5%, 50В"))
    )
    (comp (ref "C206")
      (value "22")
      (footprint "CAPC1005X06N")
      (description "Кер. ЧИП-конденсатор")
      (fields (field (name "TOLERANCE") "±5%"))
      (libsource (lib "nels_caps") (part "Кер.ЧИП конд. 0402 22пФ NPO 5%, 50В"))
    )
    (comp (ref "C207")
      (value "180")
      (footprint "CAPC1005X06N")
      (description "Кер. ЧИП-конденсатор")
      (fields (field (name "TOLERANCE") "±5%"))
      (libsource (lib "nels_caps") (part "Кер.ЧИП конд. 0402 180пФ NPO 5%, 50В"))
    )
    (comp (ref "DA1")
      (value "AS169-73")
      (footprint "SOT95P270X145-6N")
      (description "PHEMT GaAs IC SPDT Switch 300 kHz–2.5 GHz")
      (fields (field (name "MANUFACTURER") "Qorvo"))
      (libsource (lib "nels_chip") (part "Микросхема AS169-73"))
    )
    (comp (ref "DA2")
      (value "AS169-73")
      (footprint "SOT95P270X145-6N")
      (description "PHEMT GaAs IC SPDT Switch 300 kHz–2.5 GHz")
      (fields (field (name "MANUFACTURER") "Qorvo"))
      (libsource (lib "") (part "Микросхема AS169-73_1"))
    )
    (comp (ref "DA3")
      (value "PE4312C-Z")
      (footprint "QFN50P400X400X80_HS-21L")
      (description "RF Digital Step Attenuator 6-bit, 31.5 dB, 1 MHz–4 GHz")
      (fields (field (name "MANUFACTURER") "Peregrine"))
      (libsource (lib "nels_chip") (part "Микросхема PE4312C-Z"))
    )
    (comp (ref "DA4")
      (value "AS169-73")
      (footprint "SOT95P270X145-6N")
      (description "PHEMT GaAs IC SPDT Switch 300 kHz–2.5 GHz")
      (fields (field (name "MANUFACTURER") "Qorvo"))
      (libsource (lib "nels_chip") (part "Микросхема AS169-73"))
    )
    (comp (ref "DA5")
      (value "AS169-73")
      (footprint "SOT95P270X145-6N")
      (description "PHEMT GaAs IC SPDT Switch 300 kHz–2.5 GHz")
      (fields (field (name "MANUFACTURER") "Qorvo"))
      (libsource (lib "nels_chip") (part "Микросхема AS169-73"))
    )
    (comp (ref "DA6")
      (value "AS169-73")
      (footprint "SOT95P270X145-6N")
      (description "PHEMT GaAs IC SPDT Switch 300 kHz–2.5 GHz")
      (fields (field (name "MANUFACTURER") "Qorvo"))
      (libsource (lib "") (part "Микросхема AS169-73_1"))
    )
    (comp (ref "DA7")
      (value "AS169-73")
      (footprint "SOT95P270X145-6N")
      (description "PHEMT GaAs IC SPDT Switch 300 kHz–2.5 GHz")
      (fields (field (name "MANUFACTURER") "Qorvo"))
      (libsource (lib "nels_chip") (part "Микросхема AS169-73"))
    )
    (comp (ref "DA8")
      (value "AS169-73")
      (footprint "SOT95P270X145-6N")
      (description "PHEMT GaAs IC SPDT Switch 300 kHz–2.5 GHz")
      (fields (field (name "MANUFACTURER") "Qorvo"))
      (libsource (lib "") (part "Микросхема AS169-73_1"))
    )
    (comp (ref "DA9")
      (value "AS169-73")
      (footprint "SOT95P270X145-6N")
      (description "PHEMT GaAs IC SPDT Switch 300 kHz–2.5 GHz")
      (fields (field (name "MANUFACTURER") "Qorvo"))
      (libsource (lib "nels_chip") (part "Микросхема AS169-73"))
    )
    (comp (ref "DA10")
      (value "AS169-73")
      (footprint "SOT95P270X145-6N")
      (description "PHEMT GaAs IC SPDT Switch 300 kHz–2.5 GHz")
      (fields (field (name "MANUFACTURER") "Qorvo"))
      (libsource (lib "") (part "Микросхема AS169-73_1"))
    )
    (comp (ref "DA11")
      (value "AS169-73")
      (footprint "SOT95P270X145-6N")
      (description "PHEMT GaAs IC SPDT Switch 300 kHz–2.5 GHz")
      (fields (field (name "MANUFACTURER") "Qorvo"))
      (libsource (lib "nels_chip") (part "Микросхема AS169-73"))
    )
    (comp (ref "DA12")
      (value "AS169-73")
      (footprint "SOT95P270X145-6N")
      (description "PHEMT GaAs IC SPDT Switch 300 kHz–2.5 GHz")
      (fields (field (name "MANUFACTURER") "Qorvo"))
      (libsource (lib "") (part "Микросхема AS169-73_1"))
    )
    (comp (ref "DA13")
      (value "AS169-73")
      (footprint "SOT95P270X145-6N")
      (description "PHEMT GaAs IC SPDT Switch 300 kHz–2.5 GHz")
      (fields (field (name "MANUFACTURER") "Qorvo"))
      (libsource (lib "nels_chip") (part "Микросхема AS169-73"))
    )
    (comp (ref "DA14")
      (value "AS169-73")
      (footprint "SOT95P270X145-6N")
      (description "PHEMT GaAs IC SPDT Switch 300 kHz–2.5 GHz")
      (fields (field (name "MANUFACTURER") "Qorvo"))
      (libsource (lib "") (part "Микросхема AS169-73_1"))
    )
    (comp (ref "DA15")
      (value "AS169-73")
      (footprint "SOT95P270X145-6N")
      (description "PHEMT GaAs IC SPDT Switch 300 kHz–2.5 GHz")
      (fields (field (name "MANUFACTURER") "Qorvo"))
      (libsource (lib "nels_chip") (part "Микросхема AS169-73"))
    )
    (comp (ref "DA16")
      (value "AS169-73")
      (footprint "SOT95P270X145-6N")
      (description "PHEMT GaAs IC SPDT Switch 300 kHz–2.5 GHz")
      (fields (field (name "MANUFACTURER") "Qorvo"))
      (libsource (lib "") (part "Микросхема AS169-73_1"))
    )
    (comp (ref "DA17")
      (value "AS169-73")
      (footprint "SOT95P270X145-6N")
      (description "PHEMT GaAs IC SPDT Switch 300 kHz–2.5 GHz")
      (fields (field (name "MANUFACTURER") "Qorvo"))
      (libsource (lib "nels_chip") (part "Микросхема AS169-73"))
    )
    (comp (ref "DA18")
      (value "AS169-73")
      (footprint "SOT95P270X145-6N")
      (description "PHEMT GaAs IC SPDT Switch 300 kHz–2.5 GHz")
      (fields (field (name "MANUFACTURER") "Qorvo"))
      (libsource (lib "") (part "Микросхема AS169-73_1"))
    )
    (comp (ref "DA19")
      (value "AS169-73")
      (footprint "SOT95P270X145-6N")
      (description "PHEMT GaAs IC SPDT Switch 300 kHz–2.5 GHz")
      (fields (field (name "MANUFACTURER") "Qorvo"))
      (libsource (lib "nels_chip") (part "Микросхема AS169-73"))
    )
    (comp (ref "DA20")
      (value "AS169-73")
      (footprint "SOT95P270X145-6N")
      (description "PHEMT GaAs IC SPDT Switch 300 kHz–2.5 GHz")
      (fields (field (name "MANUFACTURER") "Qorvo"))
      (libsource (lib "") (part "Микросхема AS169-73_1"))
    )
    (comp (ref "L1")
      (value "560нГн")
      (footprint "INDC0805CS")
      (libsource (lib "nels_ind") (part "ЧИП индуктивность 0805CS-561X"))
    )
    (comp (ref "L2")
      (value "560нГн")
      (footprint "INDC0805CS")
      (libsource (lib "nels_ind") (part "ЧИП индуктивность 0805CS-561X"))
    )
    (comp (ref "L3")
      (value "5,6мкГн")
      (footprint "Coilcraft-1008CS")
      (description "Chip Inductors–1008CS Series (2520)")
      (fields
        (field (name "MANUFACTURER") "Сoilcraft")
        (field (name "MANUFACTURERPARTNUMBER") "1008CS-562X_E_")
      )
      (libsource (lib "nels_ind") (part "ЧИП индуктивность 1008CS-562X_"))
    )
    (comp (ref "L4")
      (value "47нГн")
      (footprint "INDC0805CS")
      (libsource (lib "nels_ind") (part "ЧИП индуктивность 0805CS-470X"))
    )
    (comp (ref "L5")
      (value "BLM18PG121SN1D")
      (footprint "INDC1608X08L")
      (description "SMD EMI Suppression Filter EMIFIL")
      (fields (field (name "MANUFACTURER") "Murata"))
      (libsource (lib "nels_ind") (part "ЧИП дроссель 0603 BLM18PG121SN1D"))
    )
    (comp (ref "L6")
      (value "150нГн")
      (footprint "INDC0805CS")
      (libsource (lib "nels_ind") (part "ЧИП индуктивность 0805CS-151XGL"))
    )
    (comp (ref "L7")
      (value "110нГн")
      (footprint "INDC0805CS")
      (libsource (lib "nels_ind") (part "ЧИП индуктивность 0805CS-111XGL"))
    )
    (comp (ref "L8")
      (value "5,6мкГн")
      (footprint "Coilcraft-1008CS")
      (description "Chip Inductors–1008CS Series (2520)")
      (fields
        (field (name "MANUFACTURER") "Сoilcraft")
        (field (name "MANUFACTURERPARTNUMBER") "1008CS-562X_E_")
      )
      (libsource (lib "nels_ind") (part "ЧИП индуктивность 1008CS-562X_"))
    )
    (comp (ref "L9")
      (value "5,6мкГн")
      (footprint "Coilcraft-1008CS")
      (description "Chip Inductors–1008CS Series (2520)")
      (fields
        (field (name "MANUFACTURER") "Сoilcraft")
        (field (name "MANUFACTURERPARTNUMBER") "1008CS-562X_E_")
      )
      (libsource (lib "nels_ind") (part "ЧИП индуктивность 1008CS-562X_"))
    )
    (comp (ref "L10")
      (value "1мкГн")
      (footprint "INDC0805CS")
      (libsource (lib "nels_ind") (part "ЧИП индуктивность 0805CS-102X"))
    )
    (comp (ref "L11")
      (value "1мкГн")
      (footprint "INDC0805CS")
      (libsource (lib "nels_ind") (part "ЧИП индуктивность 0805CS-102X"))
    )
    (comp (ref "L12")
      (value "270нГн")
      (footprint "INDC0805CS")
      (libsource (lib "nels_ind") (part "ЧИП индуктивность 0805CS-271X"))
    )
    (comp (ref "L13")
      (value "5,6мкГн")
      (footprint "Coilcraft-1008CS")
      (description "Chip Inductors–1008CS Series (2520)")
      (fields
        (field (name "MANUFACTURER") "Сoilcraft")
        (field (name "MANUFACTURERPARTNUMBER") "1008CS-562X_E_")
      )
      (libsource (lib "nels_ind") (part "ЧИП индуктивность 1008CS-562X_"))
    )
    (comp (ref "L14")
      (value "1,2мкГн")
      (footprint "Coilcraft-1008CS")
      (description "Chip Inductors–1008CS Series (2520)")
      (fields (field (name "MANUFACTURER") "Сoilcraft") (field (name "MANUFACTURERPARTNUMBER") "1008CS-122X"))
      (libsource (lib "nels_ind") (part "ЧИП индуктивность 1008CS-122X"))
    )
    (comp (ref "L15")
      (value "3,9мкГн")
      (footprint "Coilcraft-1008CS")
      (description "Chip Inductors–1008CS Series (2520)")
      (fields
        (field (name "MANUFACTURER") "Сoilcraft")
        (field (name "MANUFACTURERPARTNUMBER") "1008CS-391X_E_")
      )
      (libsource (lib "nels_ind") (part "ЧИП индуктивность 1008CS-392X"))
    )
    (comp (ref "L16")
      (value "3,9мкГн")
      (footprint "Coilcraft-1008CS")
      (description "Chip Inductors–1008CS Series (2520)")
      (fields
        (field (name "MANUFACTURER") "Сoilcraft")
        (field (name "MANUFACTURERPARTNUMBER") "1008CS-392X_E_")
      )
      (libsource (lib "nels_ind") (part "ЧИП индуктивность 1008CS-392X"))
    )
    (comp (ref "L17")
      (value "680нГн")
      (footprint "INDC0805CS")
      (libsource (lib "nels_ind") (part "ЧИП индуктивность 0805CS-681X"))
    )
    (comp (ref "L18")
      (value "1мкГн")
      (footprint "INDC0805CS")
      (libsource (lib "nels_ind") (part "ЧИП индуктивность 0805CS-102X"))
    )
    (comp (ref "L19")
      (value "1мкГн")
      (footprint "INDC0805CS")
      (libsource (lib "nels_ind") (part "ЧИП индуктивность 0805CS-102X"))
    )
    (comp (ref "L20")
      (value "470нГн")
      (footprint "INDC0805CS")
      (libsource (lib "nels_ind") (part "ЧИП индуктивность 0805CS-471X"))
    )
    (comp (ref "L21")
      (value "470нГн")
      (footprint "INDC0805CS")
      (libsource (lib "nels_ind") (part "ЧИП индуктивность 0805CS-471X"))
    )
    (comp (ref "L22")
      (value "120нГн")
      (footprint "INDC0805CS")
      (libsource (lib "nels_ind") (part "ЧИП индуктивность 0805CS-121X"))
    )
    (comp (ref "L23")
      (value "120нГн")
      (footprint "INDC0805CS")
      (libsource (lib "nels_ind") (part "ЧИП индуктивность 0805CS-121X"))
    )
    (comp (ref "L24")
      (value "1.5мкГн")
      (footprint "INDC0805CS")
      (libsource (lib "nels_ind") (part "ЧИП индуктивность 0805CS-152X"))
    )
    (comp (ref "L25")
      (value "1,8мкГн")
      (footprint "INDC0805CS")
      (description "Chip Inductors – 0805CS (2012)")
      (fields
        (field (name "MANUFACTURER") "Сoilcraft")
        (field (name "MANUFACTURERPARTNUMBER") "1812PS-683KLC")
      )
      (libsource (lib "nels_ind") (part "ЧИП индуктивность 0805CS-182X"))
    )
    (comp (ref "L26")
      (value "680нГн")
      (footprint "INDC0805CS")
      (libsource (lib "nels_ind") (part "ЧИП индуктивность 0805CS-681X"))
    )
    (comp (ref "L27")
      (value "2.2мкГн")
      (footprint "INDC0805CS")
      (libsource (lib "nels_ind") (part "ЧИП индуктивность 0805CS-222X"))
    )
    (comp (ref "L28")
      (value "2.2мкГн")
      (footprint "INDC0805CS")
      (libsource (lib "nels_ind") (part "ЧИП индуктивность 0805CS-222X"))
    )
    (comp (ref "L29")
      (value "220нГн")
      (footprint "INDC0805CS")
      (libsource (lib "nels_ind") (part "ЧИП индуктивность 0805CS-221XGL"))
    )
    (comp (ref "R1")
      (value "100")
      (footprint "RESC1005X06N")
      (description "ЧИП-резистор")
      (fields (field (name "TOLERANCE") "±5%"))
      (libsource (lib "nels_res") (part "Чип резистор 0402 100 Ом, 5%"))
    )
    (comp (ref "R2")
      (value "100")
      (footprint "RESC1005X06N")
      (description "ЧИП-резистор")
      (fields (field (name "TOLERANCE") "±5%"))
      (libsource (lib "nels_res") (part "Чип резистор 0402 100 Ом, 5%"))
    )
    (comp (ref "R3")
      (value "10к")
      (footprint "RESC1005X06N")
      (description "ЧИП-резистор")
      (fields (field (name "TOLERANCE") "±5%"))
      (libsource (lib "nels_res") (part "Чип резистор 0402 10 кОм, 5%"))
    )
    (comp (ref "R4")
      (value "10к")
      (footprint "RESC1005X06N")
      (description "ЧИП-резистор")
      (fields (field (name "TOLERANCE") "±5%"))
      (libsource (lib "") (part "Чип резистор 0402 10 кОм, 5%_2"))
    )
    (comp (ref "R5")
      (value "100")
      (footprint "RESC1005X06N")
      (description "ЧИП-резистор")
      (fields (field (name "TOLERANCE") "±5%"))
      (libsource (lib "nels_res") (part "Чип резистор 0402 100 Ом, 5%"))
    )
    (comp (ref "R6")
      (value "100")
      (footprint "RESC1005X06N")
      (description "ЧИП-резистор")
      (fields (field (name "TOLERANCE") "±5%"))
      (libsource (lib "nels_res") (part "Чип резистор 0402 100 Ом, 5%"))
    )
    (comp (ref "R7")
      (value "10к")
      (footprint "RESC1005X06N")
      (description "ЧИП-резистор")
      (fields (field (name "TOLERANCE") "±5%"))
      (libsource (lib "") (part "Чип резистор 0402 10 кОм, 5%_1"))
    )
    (comp (ref "R8")
      (value "100")
      (footprint "RESC1005X06N")
      (description "ЧИП-резистор")
      (fields (field (name "TOLERANCE") "±5%"))
      (libsource (lib "nels_res") (part "Чип резистор 0402 100 Ом, 5%"))
    )
    (comp (ref "R9")
      (value "100")
      (footprint "RESC1005X06N")
      (description "ЧИП-резистор")
      (fields (field (name "TOLERANCE") "±5%"))
      (libsource (lib "nels_res") (part "Чип резистор 0402 100 Ом, 5%"))
    )
    (comp (ref "R10")
      (value "100")
      (footprint "RESC1005X06N")
      (description "ЧИП-резистор")
      (fields (field (name "TOLERANCE") "±5%"))
      (libsource (lib "nels_res") (part "Чип резистор 0402 100 Ом, 5%"))
    )
    (comp (ref "R11")
      (value "100")
      (footprint "RESC1005X06N")
      (description "ЧИП-резистор")
      (fields (field (name "TOLERANCE") "±5%"))
      (libsource (lib "nels_res") (part "Чип резистор 0402 100 Ом, 5%"))
    )
    (comp (ref "R12")
      (value "100")
      (footprint "RESC1005X06N")
      (description "ЧИП-резистор")
      (fields (field (name "TOLERANCE") "±5%"))
      (libsource (lib "nels_res") (part "Чип резистор 0402 100 Ом, 5%"))
    )
    (comp (ref "R13")
      (value "100")
      (footprint "RESC1005X06N")
      (description "ЧИП-резистор")
      (fields (field (name "TOLERANCE") "±5%"))
      (libsource (lib "nels_res") (part "Чип резистор 0402 100 Ом, 5%"))
    )
    (comp (ref "R14")
      (value "100")
      (footprint "RESC1005X06N")
      (description "ЧИП-резистор")
      (fields (field (name "TOLERANCE") "±5%"))
      (libsource (lib "") (part "Чип резистор 0402 100 Ом, 5%_1"))
    )
    (comp (ref "R15")
      (value "100")
      (footprint "RESC1005X06N")
      (description "ЧИП-резистор")
      (fields (field (name "TOLERANCE") "±5%"))
      (libsource (lib "") (part "Чип резистор 0402 100 Ом, 5%_1"))
    )
    (comp (ref "R16")
      (value "100")
      (footprint "RESC1005X06N")
      (description "ЧИП-резистор")
      (fields (field (name "TOLERANCE") "±5%"))
      (libsource (lib "nels_res") (part "Чип резистор 0402 100 Ом, 5%"))
    )
    (comp (ref "R17")
      (value "100")
      (footprint "RESC1005X06N")
      (description "ЧИП-резистор")
      (fields (field (name "TOLERANCE") "±5%"))
      (libsource (lib "nels_res") (part "Чип резистор 0402 100 Ом, 5%"))
    )
    (comp (ref "R18")
      (value "100")
      (footprint "RESC1005X06N")
      (description "ЧИП-резистор")
      (fields (field (name "TOLERANCE") "±5%"))
      (libsource (lib "") (part "Чип резистор 0402 100 Ом, 5%_1"))
    )
    (comp (ref "R19")
      (value "100")
      (footprint "RESC1005X06N")
      (description "ЧИП-резистор")
      (fields (field (name "TOLERANCE") "±5%"))
      (libsource (lib "nels_res") (part "Чип резистор 0402 100 Ом, 5%"))
    )
    (comp (ref "R20")
      (value "100")
      (footprint "RESC1005X06N")
      (description "ЧИП-резистор")
      (fields (field (name "TOLERANCE") "±5%"))
      (libsource (lib "nels_res") (part "Чип резистор 0402 100 Ом, 5%"))
    )
    (comp (ref "R21")
      (value "100")
      (footprint "RESC1005X06N")
      (description "ЧИП-резистор")
      (fields (field (name "TOLERANCE") "±5%"))
      (libsource (lib "") (part "Чип резистор 0402 100 Ом, 5%_1"))
    )
    (comp (ref "R22")
      (value "100")
      (footprint "RESC1005X06N")
      (description "ЧИП-резистор")
      (fields (field (name "TOLERANCE") "±5%"))
      (libsource (lib "") (part "Чип резистор 0402 100 Ом, 5%_1"))
    )
    (comp (ref "R23")
      (value "100")
      (footprint "RESC1005X06N")
      (description "ЧИП-резистор")
      (fields (field (name "TOLERANCE") "±5%"))
      (libsource (lib "nels_res") (part "Чип резистор 0402 100 Ом, 5%"))
    )
    (comp (ref "R24")
      (value "100")
      (footprint "RESC1005X06N")
      (description "ЧИП-резистор")
      (fields (field (name "TOLERANCE") "±5%"))
      (libsource (lib "") (part "Чип резистор 0402 100 Ом, 5%_1"))
    )
    (comp (ref "R25")
      (value "100")
      (footprint "RESC1005X06N")
      (description "ЧИП-резистор")
      (fields (field (name "TOLERANCE") "±5%"))
      (libsource (lib "") (part "Чип резистор 0402 100 Ом, 5%_1"))
    )
    (comp (ref "R31")
      (value "100")
      (footprint "RESC1005X06N")
      (description "ЧИП-резистор")
      (fields (field (name "TOLERANCE") "±5%"))
      (libsource (lib "nels_res") (part "Чип резистор 0402 100 Ом, 5%"))
    )
    (comp (ref "R41")
      (value "100")
      (footprint "RESC1005X06N")
      (description "ЧИП-резистор")
      (fields (field (name "TOLERANCE") "±5%"))
      (libsource (lib "nels_res") (part "Чип резистор 0402 100 Ом, 5%"))
    )
    (comp (ref "R42")
      (value "100")
      (footprint "RESC1005X06N")
      (description "ЧИП-резистор")
      (fields (field (name "TOLERANCE") "±5%"))
      (libsource (lib "") (part "Чип резистор 0402 100 Ом, 5%_1"))
    )
    (comp (ref "R43")
      (value "100")
      (footprint "RESC1005X06N")
      (description "ЧИП-резистор")
      (fields (field (name "TOLERANCE") "±5%"))
      (libsource (lib "nels_res") (part "Чип резистор 0402 100 Ом, 5%"))
    )
    (comp (ref "R67")
      (value "100к")
      (footprint "RESC3216X04L")
      (description "ЧИП-резистор")
      (fields (field (name "TOLERANCE") "±5%") (field (name "MANUFACTURER") "ROHM"))
      (libsource (lib "nels_res") (part "Чип резистор 1206 100 кОм, 5%"))
    )
    (comp (ref "R70")
      (value "100")
      (footprint "RESC1005X06N")
      (description "ЧИП-резистор")
      (fields (field (name "TOLERANCE") "±5%"))
      (libsource (lib "") (part "Чип резистор 0402 100 Ом, 5%_1"))
    )
    (comp (ref "R72")
      (value "100")
      (footprint "RESC1005X06N")
      (description "ЧИП-резистор")
      (fields (field (name "TOLERANCE") "±5%"))
      (libsource (lib "nels_res") (part "Чип резистор 0402 100 Ом, 5%"))
    )
    (comp (ref "R73")
      (value "100")
      (footprint "RESC1005X06N")
      (description "ЧИП-резистор")
      (fields (field (name "TOLERANCE") "±5%"))
      (libsource (lib "") (part "Чип резистор 0402 100 Ом, 5%_1"))
    )
    (comp (ref "R74")
      (value "100")
      (footprint "RESC1005X06N")
      (description "ЧИП-резистор")
      (fields (field (name "TOLERANCE") "±5%"))
      (libsource (lib "") (part "Чип резистор 0402 100 Ом, 5%_1"))
    )
    (comp (ref "R75")
      (value "100")
      (footprint "RESC1005X06N")
      (description "ЧИП-резистор")
      (fields (field (name "TOLERANCE") "±5%"))
      (libsource (lib "nels_res") (part "Чип резистор 0402 100 Ом, 5%"))
    )
    (comp (ref "R76")
      (value "100")
      (footprint "RESC1005X06N")
      (description "ЧИП-резистор")
      (fields (field (name "TOLERANCE") "±5%"))
      (libsource (lib "nels_res") (part "Чип резистор 0402 100 Ом, 5%"))
    )
    (comp (ref "R77")
      (value "100")
      (footprint "RESC1005X06N")
      (description "ЧИП-резистор")
      (fields (field (name "TOLERANCE") "±5%"))
      (libsource (lib "") (part "Чип резистор 0402 100 Ом, 5%_1"))
    )
    (comp (ref "R78")
      (value "100")
      (footprint "RESC1005X06N")
      (description "ЧИП-резистор")
      (fields (field (name "TOLERANCE") "±5%"))
      (libsource (lib "nels_res") (part "Чип резистор 0402 100 Ом, 5%"))
    )
    (comp (ref "R79")
      (value "100")
      (footprint "RESC1005X06N")
      (description "ЧИП-резистор")
      (fields (field (name "TOLERANCE") "±5%"))
      (libsource (lib "") (part "Чип резистор 0402 100 Ом, 5%_1"))
    )
    (comp (ref "R80")
      (value "100")
      (footprint "RESC1005X06N")
      (description "ЧИП-резистор")
      (fields (field (name "TOLERANCE") "±5%"))
      (libsource (lib "") (part "Чип резистор 0402 100 Ом, 5%_1"))
    )
    (comp (ref "R81")
      (value "100")
      (footprint "RESC1005X06N")
      (description "ЧИП-резистор")
      (fields (field (name "TOLERANCE") "±5%"))
      (libsource (lib "nels_res") (part "Чип резистор 0402 100 Ом, 5%"))
    )
    (comp (ref "R82")
      (value "100")
      (footprint "RESC1005X06N")
      (description "ЧИП-резистор")
      (fields (field (name "TOLERANCE") "±5%"))
      (libsource (lib "nels_res") (part "Чип резистор 0402 100 Ом, 5%"))
    )
    (comp (ref "R83")
      (value "100")
      (footprint "RESC1005X06N")
      (description "ЧИП-резистор")
      (fields (field (name "TOLERANCE") "±5%"))
      (libsource (lib "") (part "Чип резистор 0402 100 Ом, 5%_1"))
    )
    (comp (ref "R84")
      (value "100")
      (footprint "RESC1005X06N")
      (description "ЧИП-резистор")
      (fields (field (name "TOLERANCE") "±5%"))
      (libsource (lib "") (part "Чип резистор 0402 100 Ом, 5%_1"))
    )
    (comp (ref "XW1")
      (value "SMA-JR")
      (footprint "SMA-JR")
      (description "SMA-JR Разъем SMA гнездо на плату, прямой угол")
      (libsource (lib "nels_conn") (part "Соединитель коаксиальный SMA-JR"))
    )
    (comp (ref "XW2")
      (value "SMA-JR")
      (footprint "SMA-JR")
      (description "SMA-JR Разъем SMA гнездо на плату, прямой угол")
      (libsource (lib "nels_conn") (part "Соединитель коаксиальный SMA-JR"))
    )
  )
  (nets
    (net (code "1") (name "ATT_CLK") (class "Default")
      (node (ref "R5") (pin "2") (pinfunction "2_2") (pintype "passive"))
    )
    (net (code "2") (name "ATT_DATA") (class "Default")
      (node (ref "R4") (pin "2") (pinfunction "2_2") (pintype "passive"))
    )
    (net (code "3") (name "ATT_LE0") (class "Default")
      (node (ref "R6") (pin "2") (pinfunction "2_2") (pintype "passive"))
    )
    (net (code "4") (name "BAND0_DIS") (class "Default")
      (node (ref "R13") (pin "2") (pinfunction "2_2") (pintype "passive"))
      (node (ref "R14") (pin "1") (pinfunction "1_1") (pintype "passive"))
    )
    (net (code "5") (name "BAND0_EN") (class "Default")
      (node (ref "R12") (pin "2") (pinfunction "2_2") (pintype "passive"))
      (node (ref "R15") (pin "1") (pinfunction "1_1") (pintype "passive"))
    )
    (net (code "6") (name "BAND1_DIS") (class "Default")
      (node (ref "R23") (pin "2") (pinfunction "2_2") (pintype "passive"))
      (node (ref "R24") (pin "1") (pinfunction "1_1") (pintype "passive"))
    )
    (net (code "7") (name "BAND1_EN") (class "Default")
      (node (ref "R19") (pin "2") (pinfunction "2_2") (pintype "passive"))
      (node (ref "R25") (pin "1") (pinfunction "1_1") (pintype "passive"))
    )
    (net (code "8") (name "BAND2_DIS") (class "Default")
      (node (ref "R72") (pin "2") (pinfunction "2_2") (pintype "passive"))
      (node (ref "R73") (pin "1") (pinfunction "1_1") (pintype "passive"))
    )
    (net (code "9") (name "BAND2_EN") (class "Default")
      (node (ref "R43") (pin "2") (pinfunction "2_2") (pintype "passive"))
      (node (ref "R74") (pin "1") (pinfunction "1_1") (pintype "passive"))
    )
    (net (code "10") (name "BAND3_DIS") (class "Default")
      (node (ref "R78") (pin "2") (pinfunction "2_2") (pintype "passive"))
      (node (ref "R79") (pin "1") (pinfunction "1_1") (pintype "passive"))
    )
    (net (code "11") (name "BAND3_EN") (class "Default")
      (node (ref "R76") (pin "2") (pinfunction "2_2") (pintype "passive"))
      (node (ref "R80") (pin "1") (pinfunction "1_1") (pintype "passive"))
    )
    (net (code "12") (name "BAND4_DIS") (class "Default")
      (node (ref "R82") (pin "2") (pinfunction "2_2") (pintype "passive"))
      (node (ref "R83") (pin "1") (pinfunction "1_1") (pintype "passive"))
    )
    (net (code "13") (name "BAND4_EN") (class "Default")
      (node (ref "R81") (pin "2") (pinfunction "2_2") (pintype "passive"))
      (node (ref "R84") (pin "1") (pinfunction "1_1") (pintype "passive"))
    )
    (net (code "14") (name "BAND5_DIS") (class "Default")
      (node (ref "R17") (pin "2") (pinfunction "2_2") (pintype "passive"))
      (node (ref "R18") (pin "1") (pinfunction "1_1") (pintype "passive"))
    )
    (net (code "15") (name "BAND5_EN") (class "Default")
      (node (ref "R16") (pin "2") (pinfunction "2_2") (pintype "passive"))
      (node (ref "R22") (pin "1") (pinfunction "1_1") (pintype "passive"))
    )
    (net (code "16") (name "BAND6_DIS") (class "Default")
      (node (ref "R41") (pin "2") (pinfunction "2_2") (pintype "passive"))
      (node (ref "R42") (pin "1") (pinfunction "1_1") (pintype "passive"))
    )
    (net (code "17") (name "BAND6_EN") (class "Default")
      (node (ref "R31") (pin "2") (pinfunction "2_2") (pintype "passive"))
      (node (ref "R70") (pin "1") (pinfunction "1_1") (pintype "passive"))
    )
    (net (code "18") (name "BAND7_DIS") (class "Default")
      (node (ref "R21") (pin "1") (pinfunction "1_1") (pintype "passive"))
      (node (ref "R75") (pin "2") (pinfunction "2_2") (pintype "passive"))
    )
    (net (code "19") (name "BAND7_EN") (class "Default")
      (node (ref "R20") (pin "2") (pinfunction "2_2") (pintype "passive"))
      (node (ref "R77") (pin "1") (pinfunction "1_1") (pintype "passive"))
    )
    (net (code "20") (name "BAND8_DIS") (class "Default")
      (node (ref "R10") (pin "2") (pinfunction "2_2") (pintype "passive"))
      (node (ref "R11") (pin "2") (pinfunction "2_2") (pintype "passive"))
    )
    (net (code "21") (name "BAND8_EN") (class "Default")
      (node (ref "R1") (pin "2") (pinfunction "2_2") (pintype "passive"))
      (node (ref "R2") (pin "2") (pinfunction "2_2") (pintype "passive"))
    )
    (net (code "22") (name "BPF_IN") (class "Default")
      (node (ref "C1") (pin "2") (pinfunction "2_2") (pintype "passive"))
      (node (ref "C119") (pin "2") (pinfunction "2_2") (pintype "passive"))
      (node (ref "C13") (pin "1") (pinfunction "1_1") (pintype "passive"))
      (node (ref "C170") (pin "2") (pinfunction "2_2") (pintype "passive"))
      (node (ref "C20") (pin "2") (pinfunction "2_2") (pintype "passive"))
      (node (ref "C26") (pin "2") (pinfunction "2_2") (pintype "passive"))
      (node (ref "C31") (pin "2") (pinfunction "2_2") (pintype "passive"))
      (node (ref "C47") (pin "2") (pinfunction "2_2") (pintype "passive"))
      (node (ref "C62") (pin "2") (pinfunction "2_2") (pintype "passive"))
      (node (ref "C67") (pin "2") (pinfunction "2_2") (pintype "passive"))
      (node (ref "C72") (pin "2") (pinfunction "2_2") (pintype "passive"))
      (node (ref "L7") (pin "2") (pinfunction "2_2") (pintype "passive"))
    )
    (net (code "23") (name "BPF_OUT") (class "Default")
      (node (ref "C121") (pin "1") (pinfunction "1_1") (pintype "passive"))
      (node (ref "C171") (pin "1") (pinfunction "1_1") (pintype "passive"))
      (node (ref "C27") (pin "1") (pinfunction "1_1") (pintype "passive"))
      (node (ref "C34") (pin "1") (pinfunction "1_1") (pintype "passive"))
      (node (ref "C4") (pin "1") (pinfunction "1_1") (pintype "passive"))
      (node (ref "C48") (pin "1") (pinfunction "1_1") (pintype "passive"))
      (node (ref "C52") (pin "1") (pinfunction "1_1") (pintype "passive"))
      (node (ref "C70") (pin "1") (pinfunction "1_1") (pintype "passive"))
      (node (ref "C75") (pin "1") (pinfunction "1_1") (pintype "passive"))
    )
    (net (code "24") (name "GND") (class "Default")
      (node (ref "C10") (pin "1") (pinfunction "1_1") (pintype "passive"))
      (node (ref "C116") (pin "2") (pinfunction "2_2") (pintype "passive"))
      (node (ref "C117") (pin "2") (pinfunction "2_2") (pintype "passive"))
      (node (ref "C118") (pin "1") (pinfunction "1_1") (pintype "passive"))
      (node (ref "C136") (pin "1") (pinfunction "1_1") (pintype "passive"))
      (node (ref "C14") (pin "1") (pinfunction "1_1") (pintype "passive"))
      (node (ref "C145") (pin "1") (pinfunction "1_1") (pintype "passive"))
      (node (ref "C148") (pin "2") (pinfunction "2_2") (pintype "passive"))
      (node (ref "C15") (pin "1") (pinfunction "1_1") (pintype "passive"))
      (node (ref "C161") (pin "1") (pinfunction "1_1") (pintype "passive"))
      (node (ref "C162") (pin "1") (pinfunction "1_1") (pintype "passive"))
      (node (ref "C163") (pin "2") (pinfunction "2_2") (pintype "passive"))
      (node (ref "C164") (pin "2") (pinfunction "2_2") (pintype "passive"))
      (node (ref "C165") (pin "1") (pinfunction "1_1") (pintype "passive"))
      (node (ref "C166") (pin "2") (pinfunction "2_2") (pintype "passive"))
      (node (ref "C167") (pin "2") (pinfunction "2_2") (pintype "passive"))
      (node (ref "C168") (pin "2") (pinfunction "2_2") (pintype "passive"))
      (node (ref "C169") (pin "2") (pinfunction "2_2") (pintype "passive"))
      (node (ref "C172") (pin "2") (pinfunction "2_2") (pintype "passive"))
      (node (ref "C175") (pin "1") (pinfunction "1_1") (pintype "passive"))
      (node (ref "C176") (pin "1") (pinfunction "1_1") (pintype "passive"))
      (node (ref "C177") (pin "2") (pinfunction "2_2") (pintype "passive"))
      (node (ref "C178") (pin "2") (pinfunction "2_2") (pintype "passive"))
      (node (ref "C179") (pin "2") (pinfunction "2_2") (pintype "passive"))
      (node (ref "C18") (pin "1") (pinfunction "1_1") (pintype "passive"))
      (node (ref "C180") (pin "2") (pinfunction "2_2") (pintype "passive"))
      (node (ref "C19") (pin "1") (pinfunction "1_1") (pintype "passive"))
      (node (ref "C199") (pin "1") (pinfunction "1_1") (pintype "passive"))
      (node (ref "C20") (pin "1") (pinfunction "1_1") (pintype "passive"))
      (node (ref "C201") (pin "1") (pinfunction "1_1") (pintype "passive"))
      (node (ref "C204") (pin "1") (pinfunction "1_1") (pintype "passive"))
      (node (ref "C205") (pin "1") (pinfunction "1_1") (pintype "passive"))
      (node (ref "C207") (pin "1") (pinfunction "1_1") (pintype "passive"))
      (node (ref "C21") (pin "2") (pinfunction "2_2") (pintype "passive"))
      (node (ref "C22") (pin "2") (pinfunction "2_2") (pintype "passive"))
      (node (ref "C23") (pin "2") (pinfunction "2_2") (pintype "passive"))
      (node (ref "C24") (pin "2") (pinfunction "2_2") (pintype "passive"))
      (node (ref "C25") (pin "2") (pinfunction "2_2") (pintype "passive"))
      (node (ref "C28") (pin "2") (pinfunction "2_2") (pintype "passive"))
      (node (ref "C30") (pin "1") (pinfunction "1_1") (pintype "passive"))
      (node (ref "C37") (pin "1") (pinfunction "1_1") (pintype "passive"))
      (node (ref "C38") (pin "1") (pinfunction "1_1") (pintype "passive"))
      (node (ref "C39") (pin "1") (pinfunction "1_1") (pintype "passive"))
      (node (ref "C40") (pin "1") (pinfunction "1_1") (pintype "passive"))
      (node (ref "C41") (pin "2") (pinfunction "2_2") (pintype "passive"))
      (node (ref "C42") (pin "2") (pinfunction "2_2") (pintype "passive"))
      (node (ref "C43") (pin "2") (pinfunction "2_2") (pintype "passive"))
      (node (ref "C44") (pin "2") (pinfunction "2_2") (pintype "passive"))
      (node (ref "C45") (pin "2") (pinfunction "2_2") (pintype "passive"))
      (node (ref "C46") (pin "1") (pinfunction "1_1") (pintype "passive"))
      (node (ref "C49") (pin "2") (pinfunction "2_2") (pintype "passive"))
      (node (ref "C5") (pin "2") (pinfunction "2_2") (pintype "passive"))
      (node (ref "C55") (pin "1") (pinfunction "1_1") (pintype "passive"))
      (node (ref "C56") (pin "1") (pinfunction "1_1") (pintype "passive"))
      (node (ref "C57") (pin "2") (pinfunction "2_2") (pintype "passive"))
      (node (ref "C58") (pin "2") (pinfunction "2_2") (pintype "passive"))
      (node (ref "C59") (pin "2") (pinfunction "2_2") (pintype "passive"))
      (node (ref "C6") (pin "1") (pinfunction "1_1") (pintype "passive"))
      (node (ref "C60") (pin "2") (pinfunction "2_2") (pintype "passive"))
      (node (ref "C61") (pin "1") (pinfunction "1_1") (pintype "passive"))
      (node (ref "C63") (pin "2") (pinfunction "2_2") (pintype "passive"))
      (node (ref "C64") (pin "2") (pinfunction "2_2") (pintype "passive"))
      (node (ref "C65") (pin "2") (pinfunction "2_2") (pintype "passive"))
      (node (ref "C66") (pin "2") (pinfunction "2_2") (pintype "passive"))
      (node (ref "C69") (pin "2") (pinfunction "2_2") (pintype "passive"))
      (node (ref "C7") (pin "2") (pinfunction "2_2") (pintype "passive"))
      (node (ref "C71") (pin "1") (pinfunction "1_1") (pintype "passive"))
      (node (ref "C76") (pin "2") (pinfunction "2_2") (pintype "passive"))
      (node (ref "C77") (pin "2") (pinfunction "2_2") (pintype "passive"))
      (node (ref "C78") (pin "2") (pinfunction "2_2") (pintype "passive"))
      (node (ref "C8") (pin "2") (pinfunction "2_2") (pintype "passive"))
      (node (ref "C81") (pin "1") (pinfunction "1_1") (pintype "passive"))
      (node (ref "C82") (pin "2") (pinfunction "2_2") (pintype "passive"))
      (node (ref "C83") (pin "2") (pinfunction "2_2") (pintype "passive"))
      (node (ref "C84") (pin "2") (pinfunction "2_2") (pintype "passive"))
      (node (ref "C85") (pin "2") (pinfunction "2_2") (pintype "passive"))
      (node (ref "C86") (pin "1") (pinfunction "1_1") (pintype "passive"))
      (node (ref "C87") (pin "2") (pinfunction "2_2") (pintype "passive"))
      (node (ref "C88") (pin "2") (pinfunction "2_2") (pintype "passive"))
      (node (ref "C89") (pin "2") (pinfunction "2_2") (pintype "passive"))
      (node (ref "C9") (pin "1") (pinfunction "1_1") (pintype "passive"))
      (node (ref "DA1") (pin "2") (pinfunction "GND_2") (pintype "passive"))
      (node (ref "DA10") (pin "2") (pinfunction "GND_2") (pintype "passive"))
      (node (ref "DA11") (pin "2") (pinfunction "GND_2") (pintype "passive"))
      (node (ref "DA12") (pin "2") (pinfunction "GND_2") (pintype "passive"))
      (node (ref "DA13") (pin "2") (pinfunction "GND_2") (pintype "passive"))
      (node (ref "DA14") (pin "2") (pinfunction "GND_2") (pintype "passive"))
      (node (ref "DA15") (pin "2") (pinfunction "GND_2") (pintype "passive"))
      (node (ref "DA16") (pin "2") (pinfunction "GND_2") (pintype "passive"))
      (node (ref "DA17") (pin "2") (pinfunction "GND_2") (pintype "passive"))
      (node (ref "DA18") (pin "2") (pinfunction "GND_2") (pintype "passive"))
      (node (ref "DA19") (pin "2") (pinfunction "GND_2") (pintype "passive"))
      (node (ref "DA2") (pin "2") (pinfunction "GND_2") (pintype "passive"))
      (node (ref "DA20") (pin "2") (pinfunction "GND_2") (pintype "passive"))
      (node (ref "DA3") (pin "10") (pinfunction "GND_10") (pintype "power_in"))
      (node (ref "DA3") (pin "11") (pinfunction "GND_11") (pintype "power_in"))
      (node (ref "DA3") (pin "12") (pinfunction "VSS_12") (pintype "power_in"))
      (node (ref "DA3") (pin "15") (pinfunction "C8_15") (pintype "passive"))
      (node (ref "DA3") (pin "16") (pinfunction "C4_16") (pintype "passive"))
      (node (ref "DA3") (pin "17") (pinfunction "C2_17") (pintype "passive"))
      (node (ref "DA3") (pin "19") (pinfunction "C1_19") (pintype "passive"))
      (node (ref "DA3") (pin "20") (pinfunction "C0.5_20") (pintype "passive"))
      (node (ref "DA3") (pin "21") (pinfunction "PAD_21") (pintype "power_in"))
      (node (ref "DA4") (pin "2") (pinfunction "GND_2") (pintype "passive"))
      (node (ref "DA5") (pin "2") (pinfunction "GND_2") (pintype "passive"))
      (node (ref "DA6") (pin "2") (pinfunction "GND_2") (pintype "passive"))
      (node (ref "DA7") (pin "2") (pinfunction "GND_2") (pintype "passive"))
      (node (ref "DA8") (pin "2") (pinfunction "GND_2") (pintype "passive"))
      (node (ref "DA9") (pin "2") (pinfunction "GND_2") (pintype "passive"))
      (node (ref "L12") (pin "1") (pinfunction "1_1") (pintype "passive"))
      (node (ref "L14") (pin "2") (pinfunction "2_2") (pintype "passive"))
      (node (ref "L17") (pin "2") (pinfunction "2_2") (pintype "passive"))
      (node (ref "L22") (pin "2") (pinfunction "2_2") (pintype "passive"))
      (node (ref "L23") (pin "1") (pinfunction "1_1") (pintype "passive"))
      (node (ref "L26") (pin "2") (pinfunction "2_2") (pintype "passive"))
      (node (ref "L29") (pin "2") (pinfunction "2_2") (pintype "passive"))
      (node (ref "L4") (pin "1") (pinfunction "1_1") (pintype "passive"))
      (node (ref "R3") (pin "1") (pinfunction "1_1") (pintype "passive"))
      (node (ref "R67") (pin "2") (pinfunction "2_2") (pintype "passive"))
      (node (ref "R7") (pin "2") (pinfunction "2_2") (pintype "passive"))
      (node (ref "XW1") (pin "2") (pinfunction "2_2") (pintype "passive"))
      (node (ref "XW2") (pin "2") (pinfunction "2_2") (pintype "passive"))
    )
    (net (code "25") (name "Net-(C2-Pad2)") (class "Default")
      (node (ref "C2") (pin "2") (pinfunction "2_2") (pintype "passive"))
      (node (ref "L1") (pin "1") (pinfunction "1_1") (pintype "passive"))
    )
    (net (code "26") (name "Net-(C3-Pad1)") (class "Default")
      (node (ref "C3") (pin "1") (pinfunction "1_1") (pintype "passive"))
      (node (ref "C6") (pin "2") (pinfunction "2_2") (pintype "passive"))
      (node (ref "L1") (pin "2") (pinfunction "2_2") (pintype "passive"))
      (node (ref "L4") (pin "2") (pinfunction "2_2") (pintype "passive"))
    )
    (net (code "27") (name "Net-(C3-Pad2)") (class "Default")
      (node (ref "C3") (pin "2") (pinfunction "2_2") (pintype "passive"))
      (node (ref "L2") (pin "1") (pinfunction "1_1") (pintype "passive"))
    )
    (net (code "28") (name "Net-(C11-Pad2)") (class "Default")
      (node (ref "C11") (pin "2") (pinfunction "2_2") (pintype "passive"))
      (node (ref "R67") (pin "1") (pinfunction "1_1") (pintype "passive"))
      (node (ref "XW1") (pin "1") (pinfunction "1_1") (pintype "passive"))
    )
    (net (code "29") (name "Net-(C12-Pad1)") (class "Default")
      (node (ref "C12") (pin "1") (pinfunction "1_1") (pintype "passive"))
      (node (ref "C13") (pin "2") (pinfunction "2_2") (pintype "passive"))
      (node (ref "C19") (pin "2") (pinfunction "2_2") (pintype "passive"))
      (node (ref "L6") (pin "2") (pinfunction "2_2") (pintype "passive"))
      (node (ref "L7") (pin "1") (pinfunction "1_1") (pintype "passive"))
    )
    (net (code "30") (name "Net-(C17-Pad2)") (class "Default")
      (node (ref "C17") (pin "2") (pinfunction "2_2") (pintype "passive"))
      (node (ref "XW2") (pin "1") (pinfunction "1_1") (pintype "passive"))
    )
    (net (code "31") (name "Net-(C29-Pad1)") (class "Default")
      (node (ref "C29") (pin "1") (pinfunction "1_1") (pintype "passive"))
      (node (ref "C35") (pin "1") (pinfunction "1_1") (pintype "passive"))
      (node (ref "C38") (pin "2") (pinfunction "2_2") (pintype "passive"))
      (node (ref "L3") (pin "1") (pinfunction "1_1") (pintype "passive"))
    )
    (net (code "32") (name "Net-(C32-Pad2)") (class "Default")
      (node (ref "C32") (pin "2") (pinfunction "2_2") (pintype "passive"))
      (node (ref "L10") (pin "1") (pinfunction "1_1") (pintype "passive"))
    )
    (net (code "33") (name "Net-(C33-Pad1)") (class "Default")
      (node (ref "C33") (pin "1") (pinfunction "1_1") (pintype "passive"))
      (node (ref "C37") (pin "2") (pinfunction "2_2") (pintype "passive"))
      (node (ref "L10") (pin "2") (pinfunction "2_2") (pintype "passive"))
      (node (ref "L12") (pin "2") (pinfunction "2_2") (pintype "passive"))
    )
    (net (code "34") (name "Net-(C35-Pad2)") (class "Default")
      (node (ref "C35") (pin "2") (pinfunction "2_2") (pintype "passive"))
      (node (ref "C36") (pin "1") (pinfunction "1_1") (pintype "passive"))
      (node (ref "C39") (pin "2") (pinfunction "2_2") (pintype "passive"))
      (node (ref "L3") (pin "2") (pinfunction "2_2") (pintype "passive"))
      (node (ref "L8") (pin "1") (pinfunction "1_1") (pintype "passive"))
    )
    (net (code "35") (name "Net-(C50-Pad2)") (class "Default")
      (node (ref "C50") (pin "2") (pinfunction "2_2") (pintype "passive"))
      (node (ref "L18") (pin "1") (pinfunction "1_1") (pintype "passive"))
    )
    (net (code "36") (name "Net-(C51-Pad1)") (class "Default")
      (node (ref "C51") (pin "1") (pinfunction "1_1") (pintype "passive"))
      (node (ref "C56") (pin "2") (pinfunction "2_2") (pintype "passive"))
      (node (ref "L18") (pin "2") (pinfunction "2_2") (pintype "passive"))
      (node (ref "L23") (pin "2") (pinfunction "2_2") (pintype "passive"))
    )
    (net (code "37") (name "Net-(C53-Pad2)") (class "Default")
      (node (ref "C53") (pin "2") (pinfunction "2_2") (pintype "passive"))
      (node (ref "L9") (pin "1") (pinfunction "1_1") (pintype "passive"))
    )
    (net (code "38") (name "Net-(C54-Pad1)") (class "Default")
      (node (ref "C54") (pin "1") (pinfunction "1_1") (pintype "passive"))
      (node (ref "C61") (pin "2") (pinfunction "2_2") (pintype "passive"))
      (node (ref "L14") (pin "1") (pinfunction "1_1") (pintype "passive"))
      (node (ref "L9") (pin "2") (pinfunction "2_2") (pintype "passive"))
    )
    (net (code "39") (name "Net-(C68-Pad2)") (class "Default")
      (node (ref "C68") (pin "2") (pinfunction "2_2") (pintype "passive"))
      (node (ref "L20") (pin "1") (pinfunction "1_1") (pintype "passive"))
    )
    (net (code "40") (name "Net-(C79-Pad2)") (class "Default")
      (node (ref "C79") (pin "2") (pinfunction "2_2") (pintype "passive"))
      (node (ref "L15") (pin "1") (pinfunction "1_1") (pintype "passive"))
    )
    (net (code "41") (name "Net-(C80-Pad1)") (class "Default")
      (node (ref "C80") (pin "1") (pinfunction "1_1") (pintype "passive"))
      (node (ref "C86") (pin "2") (pinfunction "2_2") (pintype "passive"))
      (node (ref "L15") (pin "2") (pinfunction "2_2") (pintype "passive"))
      (node (ref "L17") (pin "1") (pinfunction "1_1") (pintype "passive"))
    )
    (net (code "42") (name "Net-(C128-Pad1)") (class "Default")
      (node (ref "C128") (pin "1") (pinfunction "1_1") (pintype "passive"))
      (node (ref "C33") (pin "2") (pinfunction "2_2") (pintype "passive"))
      (node (ref "L11") (pin "1") (pinfunction "1_1") (pintype "passive"))
    )
    (net (code "43") (name "Net-(C135-Pad1)") (class "Default")
      (node (ref "C135") (pin "1") (pinfunction "1_1") (pintype "passive"))
      (node (ref "C54") (pin "2") (pinfunction "2_2") (pintype "passive"))
      (node (ref "L13") (pin "1") (pinfunction "1_1") (pintype "passive"))
    )
    (net (code "44") (name "Net-(C159-Pad2)") (class "Default")
      (node (ref "C159") (pin "2") (pinfunction "2_2") (pintype "passive"))
      (node (ref "L24") (pin "1") (pinfunction "1_1") (pintype "passive"))
    )
    (net (code "45") (name "Net-(C160-Pad1)") (class "Default")
      (node (ref "C160") (pin "1") (pinfunction "1_1") (pintype "passive"))
      (node (ref "C165") (pin "2") (pinfunction "2_2") (pintype "passive"))
      (node (ref "L24") (pin "2") (pinfunction "2_2") (pintype "passive"))
      (node (ref "L26") (pin "1") (pinfunction "1_1") (pintype "passive"))
    )
    (net (code "46") (name "Net-(C160-Pad2)") (class "Default")
      (node (ref "C160") (pin "2") (pinfunction "2_2") (pintype "passive"))
      (node (ref "C203") (pin "1") (pinfunction "1_1") (pintype "passive"))
      (node (ref "L25") (pin "1") (pinfunction "1_1") (pintype "passive"))
    )
    (net (code "47") (name "Net-(C161-Pad2)") (class "Default")
      (node (ref "C161") (pin "2") (pinfunction "2_2") (pintype "passive"))
      (node (ref "C90") (pin "1") (pinfunction "1_1") (pintype "passive"))
      (node (ref "L20") (pin "2") (pinfunction "2_2") (pintype "passive"))
      (node (ref "L22") (pin "1") (pinfunction "1_1") (pintype "passive"))
    )
    (net (code "48") (name "Net-(C173-Pad2)") (class "Default")
      (node (ref "C173") (pin "2") (pinfunction "2_2") (pintype "passive"))
      (node (ref "L27") (pin "1") (pinfunction "1_1") (pintype "passive"))
    )
    (net (code "49") (name "Net-(C174-Pad1)") (class "Default")
      (node (ref "C174") (pin "1") (pinfunction "1_1") (pintype "passive"))
      (node (ref "C176") (pin "2") (pinfunction "2_2") (pintype "passive"))
      (node (ref "L27") (pin "2") (pinfunction "2_2") (pintype "passive"))
      (node (ref "L29") (pin "1") (pinfunction "1_1") (pintype "passive"))
    )
    (net (code "50") (name "Net-(C174-Pad2)") (class "Default")
      (node (ref "C174") (pin "2") (pinfunction "2_2") (pintype "passive"))
      (node (ref "C206") (pin "1") (pinfunction "1_1") (pintype "passive"))
      (node (ref "L28") (pin "1") (pinfunction "1_1") (pintype "passive"))
    )
    (net (code "51") (name "Net-(C181-Pad1)") (class "Default")
      (node (ref "C181") (pin "1") (pinfunction "1_1") (pintype "passive"))
      (node (ref "C51") (pin "2") (pinfunction "2_2") (pintype "passive"))
      (node (ref "L19") (pin "1") (pinfunction "1_1") (pintype "passive"))
    )
    (net (code "52") (name "Net-(C200-Pad1)") (class "Default")
      (node (ref "C200") (pin "1") (pinfunction "1_1") (pintype "passive"))
      (node (ref "C80") (pin "2") (pinfunction "2_2") (pintype "passive"))
      (node (ref "L16") (pin "1") (pinfunction "1_1") (pintype "passive"))
    )
    (net (code "53") (name "Net-(C202-Pad1)") (class "Default")
      (node (ref "C202") (pin "1") (pinfunction "1_1") (pintype "passive"))
      (node (ref "C90") (pin "2") (pinfunction "2_2") (pintype "passive"))
      (node (ref "L21") (pin "1") (pinfunction "1_1") (pintype "passive"))
    )
    (net (code "54") (name "Net-(DA1-J1)") (class "Default")
      (node (ref "C2") (pin "1") (pinfunction "1_1") (pintype "passive"))
      (node (ref "DA1") (pin "5") (pinfunction "J1_5") (pintype "passive"))
    )
    (net (code "55") (name "Net-(DA1-J2)") (class "Default")
      (node (ref "C5") (pin "1") (pinfunction "1_1") (pintype "passive"))
      (node (ref "DA1") (pin "3") (pinfunction "J2_3") (pintype "passive"))
    )
    (net (code "56") (name "Net-(DA1-J3)") (class "Default")
      (node (ref "C1") (pin "1") (pinfunction "1_1") (pintype "passive"))
      (node (ref "DA1") (pin "1") (pinfunction "J3_1") (pintype "passive"))
    )
    (net (code "57") (name "Net-(DA1-V1)") (class "Default")
      (node (ref "C8") (pin "1") (pinfunction "1_1") (pintype "passive"))
      (node (ref "DA1") (pin "4") (pinfunction "V1_4") (pintype "passive"))
      (node (ref "R1") (pin "1") (pinfunction "1_1") (pintype "passive"))
    )
    (net (code "58") (name "Net-(DA1-V2)") (class "Default")
      (node (ref "C24") (pin "1") (pinfunction "1_1") (pintype "passive"))
      (node (ref "DA1") (pin "6") (pinfunction "V2_6") (pintype "passive"))
      (node (ref "R10") (pin "1") (pinfunction "1_1") (pintype "passive"))
    )
    (net (code "59") (name "Net-(DA2-J1)") (class "Default")
      (node (ref "DA2") (pin "5") (pinfunction "J1_5") (pintype "passive"))
      (node (ref "L2") (pin "2") (pinfunction "2_2") (pintype "passive"))
    )
    (net (code "60") (name "Net-(DA2-J2)") (class "Default")
      (node (ref "C23") (pin "1") (pinfunction "1_1") (pintype "passive"))
      (node (ref "DA2") (pin "3") (pinfunction "J2_3") (pintype "passive"))
    )
    (net (code "61") (name "Net-(DA2-J3)") (class "Default")
      (node (ref "C4") (pin "2") (pinfunction "2_2") (pintype "passive"))
      (node (ref "DA2") (pin "1") (pinfunction "J3_1") (pintype "passive"))
    )
    (net (code "62") (name "Net-(DA2-V1)") (class "Default")
      (node (ref "C7") (pin "1") (pinfunction "1_1") (pintype "passive"))
      (node (ref "DA2") (pin "4") (pinfunction "V1_4") (pintype "passive"))
      (node (ref "R2") (pin "1") (pinfunction "1_1") (pintype "passive"))
    )
    (net (code "63") (name "Net-(DA2-V2)") (class "Default")
      (node (ref "C25") (pin "1") (pinfunction "1_1") (pintype "passive"))
      (node (ref "DA2") (pin "6") (pinfunction "V2_6") (pintype "passive"))
      (node (ref "R11") (pin "1") (pinfunction "1_1") (pintype "passive"))
    )
    (net (code "64") (name "Net-(DA3-C16)") (class "Default")
      (node (ref "DA3") (pin "1") (pinfunction "C16_1") (pintype "passive"))
      (node (ref "R3") (pin "2") (pinfunction "2_2") (pintype "passive"))
    )
    (net (code "65") (name "Net-(DA3-CLOCK)") (class "Default")
      (node (ref "C14") (pin "2") (pinfunction "2_2") (pintype "passive"))
      (node (ref "DA3") (pin "4") (pinfunction "CLOCK_4") (pintype "input"))
      (node (ref "R5") (pin "1") (pinfunction "1_1") (pintype "passive"))
    )
    (net (code "66") (name "Net-(DA3-DATA)") (class "Default")
      (node (ref "DA3") (pin "3") (pinfunction "DATA_3") (pintype "input"))
      (node (ref "R4") (pin "1") (pinfunction "1_1") (pintype "passive"))
    )
    (net (code "67") (name "Net-(DA3-LE)") (class "Default")
      (node (ref "C15") (pin "2") (pinfunction "2_2") (pintype "passive"))
      (node (ref "DA3") (pin "5") (pinfunction "LE_5") (pintype "input"))
      (node (ref "R6") (pin "1") (pinfunction "1_1") (pintype "passive"))
      (node (ref "R7") (pin "1") (pinfunction "1_1") (pintype "passive"))
    )
    (net (code "68") (name "Net-(DA3-PUP1)") (class "Default")
      (node (ref "C10") (pin "2") (pinfunction "2_2") (pintype "passive"))
      (node (ref "C9") (pin "2") (pinfunction "2_2") (pintype "passive"))
      (node (ref "DA3") (pin "13") (pinfunction "P/S_13") (pintype "passive"))
      (node (ref "DA3") (pin "6") (pinfunction "Vdd_6") (pintype "power_in"))
      (node (ref "DA3") (pin "7") (pinfunction "PUP1_7") (pintype "passive"))
      (node (ref "DA3") (pin "8") (pinfunction "PUP2_8") (pintype "passive"))
      (node (ref "DA3") (pin "9") (pinfunction "Vdd_9") (pintype "power_in"))
      (node (ref "L5") (pin "1") (pinfunction "1_1") (pintype "passive"))
    )
    (net (code "69") (name "Net-(DA3-RFIN)") (class "Default")
      (node (ref "C16") (pin "1") (pinfunction "1_1") (pintype "passive"))
      (node (ref "DA3") (pin "2") (pinfunction "RFIN_2") (pintype "passive"))
    )
    (net (code "70") (name "Net-(DA3-RFOUT)") (class "Default")
      (node (ref "C12") (pin "2") (pinfunction "2_2") (pintype "passive"))
      (node (ref "C18") (pin "2") (pinfunction "2_2") (pintype "passive"))
      (node (ref "DA3") (pin "14") (pinfunction "RFOUT_14") (pintype "passive"))
      (node (ref "L6") (pin "1") (pinfunction "1_1") (pintype "passive"))
    )
    (net (code "71") (name "Net-(DA4-J1)") (class "Default")
      (node (ref "C16") (pin "2") (pinfunction "2_2") (pintype "passive"))
      (node (ref "DA4") (pin "5") (pinfunction "J1_5") (pintype "passive"))
    )
    (net (code "72") (name "Net-(DA4-J2)") (class "Default")
      (node (ref "C17") (pin "1") (pinfunction "1_1") (pintype "passive"))
      (node (ref "DA4") (pin "3") (pinfunction "J2_3") (pintype "passive"))
    )
    (net (code "73") (name "Net-(DA4-J3)") (class "Default")
      (node (ref "C11") (pin "1") (pinfunction "1_1") (pintype "passive"))
      (node (ref "DA4") (pin "1") (pinfunction "J3_1") (pintype "passive"))
    )
    (net (code "74") (name "Net-(DA4-V1)") (class "Default")
      (node (ref "C21") (pin "1") (pinfunction "1_1") (pintype "passive"))
      (node (ref "DA4") (pin "4") (pinfunction "V1_4") (pintype "passive"))
      (node (ref "R8") (pin "1") (pinfunction "1_1") (pintype "passive"))
    )
    (net (code "75") (name "Net-(DA4-V2)") (class "Default")
      (node (ref "C22") (pin "1") (pinfunction "1_1") (pintype "passive"))
      (node (ref "DA4") (pin "6") (pinfunction "V2_6") (pintype "passive"))
      (node (ref "R9") (pin "1") (pinfunction "1_1") (pintype "passive"))
    )
    (net (code "76") (name "Net-(DA5-J1)") (class "Default")
      (node (ref "C29") (pin "2") (pinfunction "2_2") (pintype "passive"))
      (node (ref "DA5") (pin "5") (pinfunction "J1_5") (pintype "passive"))
    )
    (net (code "77") (name "Net-(DA5-J2)") (class "Default")
      (node (ref "C28") (pin "1") (pinfunction "1_1") (pintype "passive"))
      (node (ref "DA5") (pin "3") (pinfunction "J2_3") (pintype "passive"))
    )
    (net (code "78") (name "Net-(DA5-J3)") (class "Default")
      (node (ref "C26") (pin "1") (pinfunction "1_1") (pintype "passive"))
      (node (ref "DA5") (pin "1") (pinfunction "J3_1") (pintype "passive"))
    )
    (net (code "79") (name "Net-(DA5-V1)") (class "Default")
      (node (ref "C41") (pin "1") (pinfunction "1_1") (pintype "passive"))
      (node (ref "DA5") (pin "4") (pinfunction "V1_4") (pintype "passive"))
      (node (ref "R12") (pin "1") (pinfunction "1_1") (pintype "passive"))
    )
    (net (code "80") (name "Net-(DA5-V2)") (class "Default")
      (node (ref "C42") (pin "1") (pinfunction "1_1") (pintype "passive"))
      (node (ref "DA5") (pin "6") (pinfunction "V2_6") (pintype "passive"))
      (node (ref "R13") (pin "1") (pinfunction "1_1") (pintype "passive"))
    )
    (net (code "81") (name "Net-(DA6-J1)") (class "Default")
      (node (ref "C36") (pin "2") (pinfunction "2_2") (pintype "passive"))
      (node (ref "C40") (pin "2") (pinfunction "2_2") (pintype "passive"))
      (node (ref "DA6") (pin "5") (pinfunction "J1_5") (pintype "passive"))
      (node (ref "L8") (pin "2") (pinfunction "2_2") (pintype "passive"))
    )
    (net (code "82") (name "Net-(DA6-J2)") (class "Default")
      (node (ref "C30") (pin "2") (pinfunction "2_2") (pintype "passive"))
      (node (ref "DA6") (pin "3") (pinfunction "J2_3") (pintype "passive"))
    )
    (net (code "83") (name "Net-(DA6-J3)") (class "Default")
      (node (ref "C27") (pin "2") (pinfunction "2_2") (pintype "passive"))
      (node (ref "DA6") (pin "1") (pinfunction "J3_1") (pintype "passive"))
    )
    (net (code "84") (name "Net-(DA6-V1)") (class "Default")
      (node (ref "C45") (pin "1") (pinfunction "1_1") (pintype "passive"))
      (node (ref "DA6") (pin "4") (pinfunction "V1_4") (pintype "passive"))
      (node (ref "R15") (pin "2") (pinfunction "2_2") (pintype "passive"))
    )
    (net (code "85") (name "Net-(DA6-V2)") (class "Default")
      (node (ref "C44") (pin "1") (pinfunction "1_1") (pintype "passive"))
      (node (ref "DA6") (pin "6") (pinfunction "V2_6") (pintype "passive"))
      (node (ref "R14") (pin "2") (pinfunction "2_2") (pintype "passive"))
    )
    (net (code "86") (name "Net-(DA7-J1)") (class "Default")
      (node (ref "C32") (pin "1") (pinfunction "1_1") (pintype "passive"))
      (node (ref "DA7") (pin "5") (pinfunction "J1_5") (pintype "passive"))
    )
    (net (code "87") (name "Net-(DA7-J2)") (class "Default")
      (node (ref "C43") (pin "1") (pinfunction "1_1") (pintype "passive"))
      (node (ref "DA7") (pin "3") (pinfunction "J2_3") (pintype "passive"))
    )
    (net (code "88") (name "Net-(DA7-J3)") (class "Default")
      (node (ref "C31") (pin "1") (pinfunction "1_1") (pintype "passive"))
      (node (ref "DA7") (pin "1") (pinfunction "J3_1") (pintype "passive"))
    )
    (net (code "89") (name "Net-(DA7-V1)") (class "Default")
      (node (ref "C57") (pin "1") (pinfunction "1_1") (pintype "passive"))
      (node (ref "DA7") (pin "4") (pinfunction "V1_4") (pintype "passive"))
      (node (ref "R16") (pin "1") (pinfunction "1_1") (pintype "passive"))
    )
    (net (code "90") (name "Net-(DA7-V2)") (class "Default")
      (node (ref "C58") (pin "1") (pinfunction "1_1") (pintype "passive"))
      (node (ref "DA7") (pin "6") (pinfunction "V2_6") (pintype "passive"))
      (node (ref "R17") (pin "1") (pinfunction "1_1") (pintype "passive"))
    )
    (net (code "91") (name "Net-(DA8-J1)") (class "Default")
      (node (ref "C128") (pin "2") (pinfunction "2_2") (pintype "passive"))
      (node (ref "C136") (pin "2") (pinfunction "2_2") (pintype "passive"))
      (node (ref "DA8") (pin "5") (pinfunction "J1_5") (pintype "passive"))
      (node (ref "L11") (pin "2") (pinfunction "2_2") (pintype "passive"))
    )
    (net (code "92") (name "Net-(DA8-J2)") (class "Default")
      (node (ref "C46") (pin "2") (pinfunction "2_2") (pintype "passive"))
      (node (ref "DA8") (pin "3") (pinfunction "J2_3") (pintype "passive"))
    )
    (net (code "93") (name "Net-(DA8-J3)") (class "Default")
      (node (ref "C34") (pin "2") (pinfunction "2_2") (pintype "passive"))
      (node (ref "DA8") (pin "1") (pinfunction "J3_1") (pintype "passive"))
    )
    (net (code "94") (name "Net-(DA8-V1)") (class "Default")
      (node (ref "C60") (pin "1") (pinfunction "1_1") (pintype "passive"))
      (node (ref "DA8") (pin "4") (pinfunction "V1_4") (pintype "passive"))
      (node (ref "R22") (pin "2") (pinfunction "2_2") (pintype "passive"))
    )
    (net (code "95") (name "Net-(DA8-V2)") (class "Default")
      (node (ref "C59") (pin "1") (pinfunction "1_1") (pintype "passive"))
      (node (ref "DA8") (pin "6") (pinfunction "V2_6") (pintype "passive"))
      (node (ref "R18") (pin "2") (pinfunction "2_2") (pintype "passive"))
    )
    (net (code "96") (name "Net-(DA9-J1)") (class "Default")
      (node (ref "C53") (pin "1") (pinfunction "1_1") (pintype "passive"))
      (node (ref "DA9") (pin "5") (pinfunction "J1_5") (pintype "passive"))
    )
    (net (code "97") (name "Net-(DA9-J2)") (class "Default")
      (node (ref "C49") (pin "1") (pinfunction "1_1") (pintype "passive"))
      (node (ref "DA9") (pin "3") (pinfunction "J2_3") (pintype "passive"))
    )
    (net (code "98") (name "Net-(DA9-J3)") (class "Default")
      (node (ref "C47") (pin "1") (pinfunction "1_1") (pintype "passive"))
      (node (ref "DA9") (pin "1") (pinfunction "J3_1") (pintype "passive"))
    )
    (net (code "99") (name "Net-(DA9-V1)") (class "Default")
      (node (ref "C63") (pin "1") (pinfunction "1_1") (pintype "passive"))
      (node (ref "DA9") (pin "4") (pinfunction "V1_4") (pintype "passive"))
      (node (ref "R19") (pin "1") (pinfunction "1_1") (pintype "passive"))
    )
    (net (code "100") (name "Net-(DA9-V2)") (class "Default")
      (node (ref "C64") (pin "1") (pinfunction "1_1") (pintype "passive"))
      (node (ref "DA9") (pin "6") (pinfunction "V2_6") (pintype "passive"))
      (node (ref "R23") (pin "1") (pinfunction "1_1") (pintype "passive"))
    )
    (net (code "101") (name "Net-(DA10-J1)") (class "Default")
      (node (ref "C135") (pin "2") (pinfunction "2_2") (pintype "passive"))
      (node (ref "C145") (pin "2") (pinfunction "2_2") (pintype "passive"))
      (node (ref "DA10") (pin "5") (pinfunction "J1_5") (pintype "passive"))
      (node (ref "L13") (pin "2") (pinfunction "2_2") (pintype "passive"))
    )
    (net (code "102") (name "Net-(DA10-J2)") (class "Default")
      (node (ref "C55") (pin "2") (pinfunction "2_2") (pintype "passive"))
      (node (ref "DA10") (pin "3") (pinfunction "J2_3") (pintype "passive"))
    )
    (net (code "103") (name "Net-(DA10-J3)") (class "Default")
      (node (ref "C48") (pin "2") (pinfunction "2_2") (pintype "passive"))
      (node (ref "DA10") (pin "1") (pinfunction "J3_1") (pintype "passive"))
    )
    (net (code "104") (name "Net-(DA10-V1)") (class "Default")
      (node (ref "C69") (pin "1") (pinfunction "1_1") (pintype "passive"))
      (node (ref "DA10") (pin "4") (pinfunction "V1_4") (pintype "passive"))
      (node (ref "R25") (pin "2") (pinfunction "2_2") (pintype "passive"))
    )
    (net (code "105") (name "Net-(DA10-V2)") (class "Default")
      (node (ref "C66") (pin "1") (pinfunction "1_1") (pintype "passive"))
      (node (ref "DA10") (pin "6") (pinfunction "V2_6") (pintype "passive"))
      (node (ref "R24") (pin "2") (pinfunction "2_2") (pintype "passive"))
    )
    (net (code "106") (name "Net-(DA11-J1)") (class "Default")
      (node (ref "C50") (pin "1") (pinfunction "1_1") (pintype "passive"))
      (node (ref "DA11") (pin "5") (pinfunction "J1_5") (pintype "passive"))
    )
    (net (code "107") (name "Net-(DA11-J2)") (class "Default")
      (node (ref "C65") (pin "1") (pinfunction "1_1") (pintype "passive"))
      (node (ref "DA11") (pin "3") (pinfunction "J2_3") (pintype "passive"))
    )
    (net (code "108") (name "Net-(DA11-J3)") (class "Default")
      (node (ref "C62") (pin "1") (pinfunction "1_1") (pintype "passive"))
      (node (ref "DA11") (pin "1") (pinfunction "J3_1") (pintype "passive"))
    )
    (net (code "109") (name "Net-(DA11-V1)") (class "Default")
      (node (ref "C82") (pin "1") (pinfunction "1_1") (pintype "passive"))
      (node (ref "DA11") (pin "4") (pinfunction "V1_4") (pintype "passive"))
      (node (ref "R31") (pin "1") (pinfunction "1_1") (pintype "passive"))
    )
    (net (code "110") (name "Net-(DA11-V2)") (class "Default")
      (node (ref "C83") (pin "1") (pinfunction "1_1") (pintype "passive"))
      (node (ref "DA11") (pin "6") (pinfunction "V2_6") (pintype "passive"))
      (node (ref "R41") (pin "1") (pinfunction "1_1") (pintype "passive"))
    )
    (net (code "111") (name "Net-(DA12-J1)") (class "Default")
      (node (ref "C181") (pin "2") (pinfunction "2_2") (pintype "passive"))
      (node (ref "C199") (pin "2") (pinfunction "2_2") (pintype "passive"))
      (node (ref "DA12") (pin "5") (pinfunction "J1_5") (pintype "passive"))
      (node (ref "L19") (pin "2") (pinfunction "2_2") (pintype "passive"))
    )
    (net (code "112") (name "Net-(DA12-J2)") (class "Default")
      (node (ref "C71") (pin "2") (pinfunction "2_2") (pintype "passive"))
      (node (ref "DA12") (pin "3") (pinfunction "J2_3") (pintype "passive"))
    )
    (net (code "113") (name "Net-(DA12-J3)") (class "Default")
      (node (ref "C52") (pin "2") (pinfunction "2_2") (pintype "passive"))
      (node (ref "DA12") (pin "1") (pinfunction "J3_1") (pintype "passive"))
    )
    (net (code "114") (name "Net-(DA12-V1)") (class "Default")
      (node (ref "C85") (pin "1") (pinfunction "1_1") (pintype "passive"))
      (node (ref "DA12") (pin "4") (pinfunction "V1_4") (pintype "passive"))
      (node (ref "R70") (pin "2") (pinfunction "2_2") (pintype "passive"))
    )
    (net (code "115") (name "Net-(DA12-V2)") (class "Default")
      (node (ref "C84") (pin "1") (pinfunction "1_1") (pintype "passive"))
      (node (ref "DA12") (pin "6") (pinfunction "V2_6") (pintype "passive"))
      (node (ref "R42") (pin "2") (pinfunction "2_2") (pintype "passive"))
    )
    (net (code "116") (name "Net-(DA13-J1)") (class "Default")
      (node (ref "C79") (pin "1") (pinfunction "1_1") (pintype "passive"))
      (node (ref "DA13") (pin "5") (pinfunction "J1_5") (pintype "passive"))
    )
    (net (code "117") (name "Net-(DA13-J2)") (class "Default")
      (node (ref "C76") (pin "1") (pinfunction "1_1") (pintype "passive"))
      (node (ref "DA13") (pin "3") (pinfunction "J2_3") (pintype "passive"))
    )
    (net (code "118") (name "Net-(DA13-J3)") (class "Default")
      (node (ref "C72") (pin "1") (pinfunction "1_1") (pintype "passive"))
      (node (ref "DA13") (pin "1") (pinfunction "J3_1") (pintype "passive"))
    )
    (net (code "119") (name "Net-(DA13-V1)") (class "Default")
      (node (ref "C87") (pin "1") (pinfunction "1_1") (pintype "passive"))
      (node (ref "DA13") (pin "4") (pinfunction "V1_4") (pintype "passive"))
      (node (ref "R43") (pin "1") (pinfunction "1_1") (pintype "passive"))
    )
    (net (code "120") (name "Net-(DA13-V2)") (class "Default")
      (node (ref "C88") (pin "1") (pinfunction "1_1") (pintype "passive"))
      (node (ref "DA13") (pin "6") (pinfunction "V2_6") (pintype "passive"))
      (node (ref "R72") (pin "1") (pinfunction "1_1") (pintype "passive"))
    )
    (net (code "121") (name "Net-(DA14-J1)") (class "Default")
      (node (ref "C200") (pin "2") (pinfunction "2_2") (pintype "passive"))
      (node (ref "C201") (pin "2") (pinfunction "2_2") (pintype "passive"))
      (node (ref "DA14") (pin "5") (pinfunction "J1_5") (pintype "passive"))
      (node (ref "L16") (pin "2") (pinfunction "2_2") (pintype "passive"))
    )
    (net (code "122") (name "Net-(DA14-J2)") (class "Default")
      (node (ref "C81") (pin "2") (pinfunction "2_2") (pintype "passive"))
      (node (ref "DA14") (pin "3") (pinfunction "J2_3") (pintype "passive"))
    )
    (net (code "123") (name "Net-(DA14-J3)") (class "Default")
      (node (ref "C75") (pin "2") (pinfunction "2_2") (pintype "passive"))
      (node (ref "DA14") (pin "1") (pinfunction "J3_1") (pintype "passive"))
    )
    (net (code "124") (name "Net-(DA14-V1)") (class "Default")
      (node (ref "C117") (pin "1") (pinfunction "1_1") (pintype "passive"))
      (node (ref "DA14") (pin "4") (pinfunction "V1_4") (pintype "passive"))
      (node (ref "R74") (pin "2") (pinfunction "2_2") (pintype "passive"))
    )
    (net (code "125") (name "Net-(DA14-V2)") (class "Default")
      (node (ref "C116") (pin "1") (pinfunction "1_1") (pintype "passive"))
      (node (ref "DA14") (pin "6") (pinfunction "V2_6") (pintype "passive"))
      (node (ref "R73") (pin "2") (pinfunction "2_2") (pintype "passive"))
    )
    (net (code "126") (name "Net-(DA15-J1)") (class "Default")
      (node (ref "C68") (pin "1") (pinfunction "1_1") (pintype "passive"))
      (node (ref "DA15") (pin "5") (pinfunction "J1_5") (pintype "passive"))
    )
    (net (code "127") (name "Net-(DA15-J2)") (class "Default")
      (node (ref "C89") (pin "1") (pinfunction "1_1") (pintype "passive"))
      (node (ref "DA15") (pin "3") (pinfunction "J2_3") (pintype "passive"))
    )
    (net (code "128") (name "Net-(DA15-J3)") (class "Default")
      (node (ref "C67") (pin "1") (pinfunction "1_1") (pintype "passive"))
      (node (ref "DA15") (pin "1") (pinfunction "J3_1") (pintype "passive"))
    )
    (net (code "129") (name "Net-(DA15-V1)") (class "Default")
      (node (ref "C78") (pin "1") (pinfunction "1_1") (pintype "passive"))
      (node (ref "DA15") (pin "4") (pinfunction "V1_4") (pintype "passive"))
      (node (ref "R20") (pin "1") (pinfunction "1_1") (pintype "passive"))
    )
    (net (code "130") (name "Net-(DA15-V2)") (class "Default")
      (node (ref "C163") (pin "1") (pinfunction "1_1") (pintype "passive"))
      (node (ref "DA15") (pin "6") (pinfunction "V2_6") (pintype "passive"))
      (node (ref "R75") (pin "1") (pinfunction "1_1") (pintype "passive"))
    )
    (net (code "131") (name "Net-(DA16-J1)") (class "Default")
      (node (ref "C202") (pin "2") (pinfunction "2_2") (pintype "passive"))
      (node (ref "C204") (pin "2") (pinfunction "2_2") (pintype "passive"))
      (node (ref "DA16") (pin "5") (pinfunction "J1_5") (pintype "passive"))
      (node (ref "L21") (pin "2") (pinfunction "2_2") (pintype "passive"))
    )
    (net (code "132") (name "Net-(DA16-J2)") (class "Default")
      (node (ref "C118") (pin "2") (pinfunction "2_2") (pintype "passive"))
      (node (ref "DA16") (pin "3") (pinfunction "J2_3") (pintype "passive"))
    )
    (net (code "133") (name "Net-(DA16-J3)") (class "Default")
      (node (ref "C70") (pin "2") (pinfunction "2_2") (pintype "passive"))
      (node (ref "DA16") (pin "1") (pinfunction "J3_1") (pintype "passive"))
    )
    (net (code "134") (name "Net-(DA16-V1)") (class "Default")
      (node (ref "C164") (pin "1") (pinfunction "1_1") (pintype "passive"))
      (node (ref "DA16") (pin "4") (pinfunction "V1_4") (pintype "passive"))
      (node (ref "R77") (pin "2") (pinfunction "2_2") (pintype "passive"))
    )
    (net (code "135") (name "Net-(DA16-V2)") (class "Default")
      (node (ref "C77") (pin "1") (pinfunction "1_1") (pintype "passive"))
      (node (ref "DA16") (pin "6") (pinfunction "V2_6") (pintype "passive"))
      (node (ref "R21") (pin "2") (pinfunction "2_2") (pintype "passive"))
    )
    (net (code "136") (name "Net-(DA17-J1)") (class "Default")
      (node (ref "C159") (pin "1") (pinfunction "1_1") (pintype "passive"))
      (node (ref "DA17") (pin "5") (pinfunction "J1_5") (pintype "passive"))
    )
    (net (code "137") (name "Net-(DA17-J2)") (class "Default")
      (node (ref "C148") (pin "1") (pinfunction "1_1") (pintype "passive"))
      (node (ref "DA17") (pin "3") (pinfunction "J2_3") (pintype "passive"))
    )
    (net (code "138") (name "Net-(DA17-J3)") (class "Default")
      (node (ref "C119") (pin "1") (pinfunction "1_1") (pintype "passive"))
      (node (ref "DA17") (pin "1") (pinfunction "J3_1") (pintype "passive"))
    )
    (net (code "139") (name "Net-(DA17-V1)") (class "Default")
      (node (ref "C166") (pin "1") (pinfunction "1_1") (pintype "passive"))
      (node (ref "DA17") (pin "4") (pinfunction "V1_4") (pintype "passive"))
      (node (ref "R76") (pin "1") (pinfunction "1_1") (pintype "passive"))
    )
    (net (code "140") (name "Net-(DA17-V2)") (class "Default")
      (node (ref "C167") (pin "1") (pinfunction "1_1") (pintype "passive"))
      (node (ref "DA17") (pin "6") (pinfunction "V2_6") (pintype "passive"))
      (node (ref "R78") (pin "1") (pinfunction "1_1") (pintype "passive"))
    )
    (net (code "141") (name "Net-(DA18-J1)") (class "Default")
      (node (ref "C203") (pin "2") (pinfunction "2_2") (pintype "passive"))
      (node (ref "C205") (pin "2") (pinfunction "2_2") (pintype "passive"))
      (node (ref "DA18") (pin "5") (pinfunction "J1_5") (pintype "passive"))
      (node (ref "L25") (pin "2") (pinfunction "2_2") (pintype "passive"))
    )
    (net (code "142") (name "Net-(DA18-J2)") (class "Default")
      (node (ref "C162") (pin "2") (pinfunction "2_2") (pintype "passive"))
      (node (ref "DA18") (pin "3") (pinfunction "J2_3") (pintype "passive"))
    )
    (net (code "143") (name "Net-(DA18-J3)") (class "Default")
      (node (ref "C121") (pin "2") (pinfunction "2_2") (pintype "passive"))
      (node (ref "DA18") (pin "1") (pinfunction "J3_1") (pintype "passive"))
    )
    (net (code "144") (name "Net-(DA18-V1)") (class "Default")
      (node (ref "C169") (pin "1") (pinfunction "1_1") (pintype "passive"))
      (node (ref "DA18") (pin "4") (pinfunction "V1_4") (pintype "passive"))
      (node (ref "R80") (pin "2") (pinfunction "2_2") (pintype "passive"))
    )
    (net (code "145") (name "Net-(DA18-V2)") (class "Default")
      (node (ref "C168") (pin "1") (pinfunction "1_1") (pintype "passive"))
      (node (ref "DA18") (pin "6") (pinfunction "V2_6") (pintype "passive"))
      (node (ref "R79") (pin "2") (pinfunction "2_2") (pintype "passive"))
    )
    (net (code "146") (name "Net-(DA19-J1)") (class "Default")
      (node (ref "C173") (pin "1") (pinfunction "1_1") (pintype "passive"))
      (node (ref "DA19") (pin "5") (pinfunction "J1_5") (pintype "passive"))
    )
    (net (code "147") (name "Net-(DA19-J2)") (class "Default")
      (node (ref "C172") (pin "1") (pinfunction "1_1") (pintype "passive"))
      (node (ref "DA19") (pin "3") (pinfunction "J2_3") (pintype "passive"))
    )
    (net (code "148") (name "Net-(DA19-J3)") (class "Default")
      (node (ref "C170") (pin "1") (pinfunction "1_1") (pintype "passive"))
      (node (ref "DA19") (pin "1") (pinfunction "J3_1") (pintype "passive"))
    )
    (net (code "149") (name "Net-(DA19-V1)") (class "Default")
      (node (ref "C177") (pin "1") (pinfunction "1_1") (pintype "passive"))
      (node (ref "DA19") (pin "4") (pinfunction "V1_4") (pintype "passive"))
      (node (ref "R81") (pin "1") (pinfunction "1_1") (pintype "passive"))
    )
    (net (code "150") (name "Net-(DA19-V2)") (class "Default")
      (node (ref "C178") (pin "1") (pinfunction "1_1") (pintype "passive"))
      (node (ref "DA19") (pin "6") (pinfunction "V2_6") (pintype "passive"))
      (node (ref "R82") (pin "1") (pinfunction "1_1") (pintype "passive"))
    )
    (net (code "151") (name "Net-(DA20-J1)") (class "Default")
      (node (ref "C206") (pin "2") (pinfunction "2_2") (pintype "passive"))
      (node (ref "C207") (pin "2") (pinfunction "2_2") (pintype "passive"))
      (node (ref "DA20") (pin "5") (pinfunction "J1_5") (pintype "passive"))
      (node (ref "L28") (pin "2") (pinfunction "2_2") (pintype "passive"))
    )
    (net (code "152") (name "Net-(DA20-J2)") (class "Default")
      (node (ref "C175") (pin "2") (pinfunction "2_2") (pintype "passive"))
      (node (ref "DA20") (pin "3") (pinfunction "J2_3") (pintype "passive"))
    )
    (net (code "153") (name "Net-(DA20-J3)") (class "Default")
      (node (ref "C171") (pin "2") (pinfunction "2_2") (pintype "passive"))
      (node (ref "DA20") (pin "1") (pinfunction "J3_1") (pintype "passive"))
    )
    (net (code "154") (name "Net-(DA20-V1)") (class "Default")
      (node (ref "C180") (pin "1") (pinfunction "1_1") (pintype "passive"))
      (node (ref "DA20") (pin "4") (pinfunction "V1_4") (pintype "passive"))
      (node (ref "R84") (pin "2") (pinfunction "2_2") (pintype "passive"))
    )
    (net (code "155") (name "Net-(DA20-V2)") (class "Default")
      (node (ref "C179") (pin "1") (pinfunction "1_1") (pintype "passive"))
      (node (ref "DA20") (pin "6") (pinfunction "V2_6") (pintype "passive"))
      (node (ref "R83") (pin "2") (pinfunction "2_2") (pintype "passive"))
    )
    (net (code "156") (name "RF_3V3") (class "Default")
      (node (ref "L5") (pin "2") (pinfunction "2_2") (pintype "passive"))
    )
    (net (code "157") (name "RX_EN") (class "Default")
      (node (ref "R8") (pin "2") (pinfunction "2_2") (pintype "passive"))
    )
    (net (code "158") (name "TX_EN") (class "Default")
      (node (ref "R9") (pin "2") (pinfunction "2_2") (pintype "passive"))
    )
    (net (code "159") (name "unconnected-(DA1-GND-Pad5)") (class "Default")
      (node (ref "DA1") (pin "5") (pinfunction "GND_5") (pintype "passive"))
    )
    (net (code "160") (name "unconnected-(DA2-GND-Pad5)") (class "Default")
      (node (ref "DA2") (pin "5") (pinfunction "GND_5") (pintype "passive"))
    )
    (net (code "161") (name "unconnected-(DA4-GND-Pad5)") (class "Default")
      (node (ref "DA4") (pin "5") (pinfunction "GND_5") (pintype "passive"))
    )
    (net (code "162") (name "unconnected-(DA5-GND-Pad5)") (class "Default")
      (node (ref "DA5") (pin "5") (pinfunction "GND_5") (pintype "passive"))
    )
    (net (code "163") (name "unconnected-(DA6-GND-Pad5)") (class "Default")
      (node (ref "DA6") (pin "5") (pinfunction "GND_5") (pintype "passive"))
    )
    (net (code "164") (name "unconnected-(DA7-GND-Pad5)") (class "Default")
      (node (ref "DA7") (pin "5") (pinfunction "GND_5") (pintype "passive"))
    )
    (net (code "165") (name "unconnected-(DA8-GND-Pad5)") (class "Default")
      (node (ref "DA8") (pin "5") (pinfunction "GND_5") (pintype "passive"))
    )
    (net (code "166") (name "unconnected-(DA9-GND-Pad5)") (class "Default")
      (node (ref "DA9") (pin "5") (pinfunction "GND_5") (pintype "passive"))
    )
    (net (code "167") (name "unconnected-(DA10-GND-Pad5)") (class "Default")
      (node (ref "DA10") (pin "5") (pinfunction "GND_5") (pintype "passive"))
    )
    (net (code "168") (name "unconnected-(DA11-GND-Pad5)") (class "Default")
      (node (ref "DA11") (pin "5") (pinfunction "GND_5") (pintype "passive"))
    )
    (net (code "169") (name "unconnected-(DA12-GND-Pad5)") (class "Default")
      (node (ref "DA12") (pin "5") (pinfunction "GND_5") (pintype "passive"))
    )
    (net (code "170") (name "unconnected-(DA13-GND-Pad5)") (class "Default")
      (node (ref "DA13") (pin "5") (pinfunction "GND_5") (pintype "passive"))
    )
    (net (code "171") (name "unconnected-(DA14-GND-Pad5)") (class "Default")
      (node (ref "DA14") (pin "5") (pinfunction "GND_5") (pintype "passive"))
    )
    (net (code "172") (name "unconnected-(DA15-GND-Pad5)") (class "Default")
      (node (ref "DA15") (pin "5") (pinfunction "GND_5") (pintype "passive"))
    )
    (net (code "173") (name "unconnected-(DA16-GND-Pad5)") (class "Default")
      (node (ref "DA16") (pin "5") (pinfunction "GND_5") (pintype "passive"))
    )
    (net (code "174") (name "unconnected-(DA17-GND-Pad5)") (class "Default")
      (node (ref "DA17") (pin "5") (pinfunction "GND_5") (pintype "passive"))
    )
    (net (code "175") (name "unconnected-(DA18-GND-Pad5)") (class "Default")
      (node (ref "DA18") (pin "5") (pinfunction "GND_5") (pintype "passive"))
    )
    (net (code "176") (name "unconnected-(DA19-GND-Pad5)") (class "Default")
      (node (ref "DA19") (pin "5") (pinfunction "GND_5") (pintype "passive"))
    )
    (net (code "177") (name "unconnected-(DA20-GND-Pad5)") (class "Default")
      (node (ref "DA20") (pin "5") (pinfunction "GND_5") (pintype "passive"))
    )
  )
)
